# keyboardDesignV1.net
KiCad netlist of a schematic drawn in EAGLE
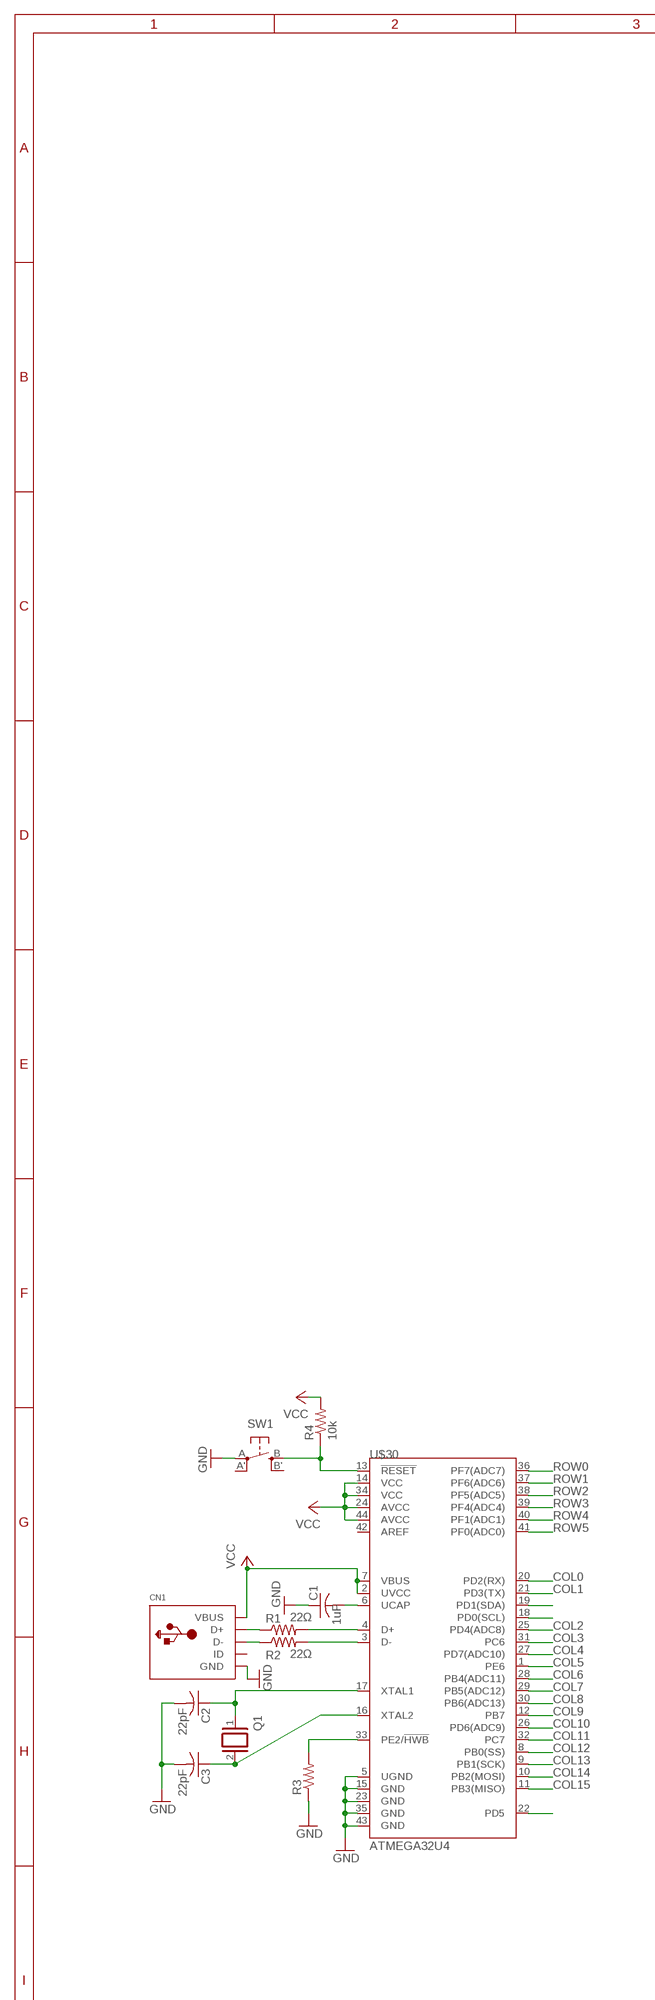
[diagram p0: schematic, sheet 1, part 1 of 2]
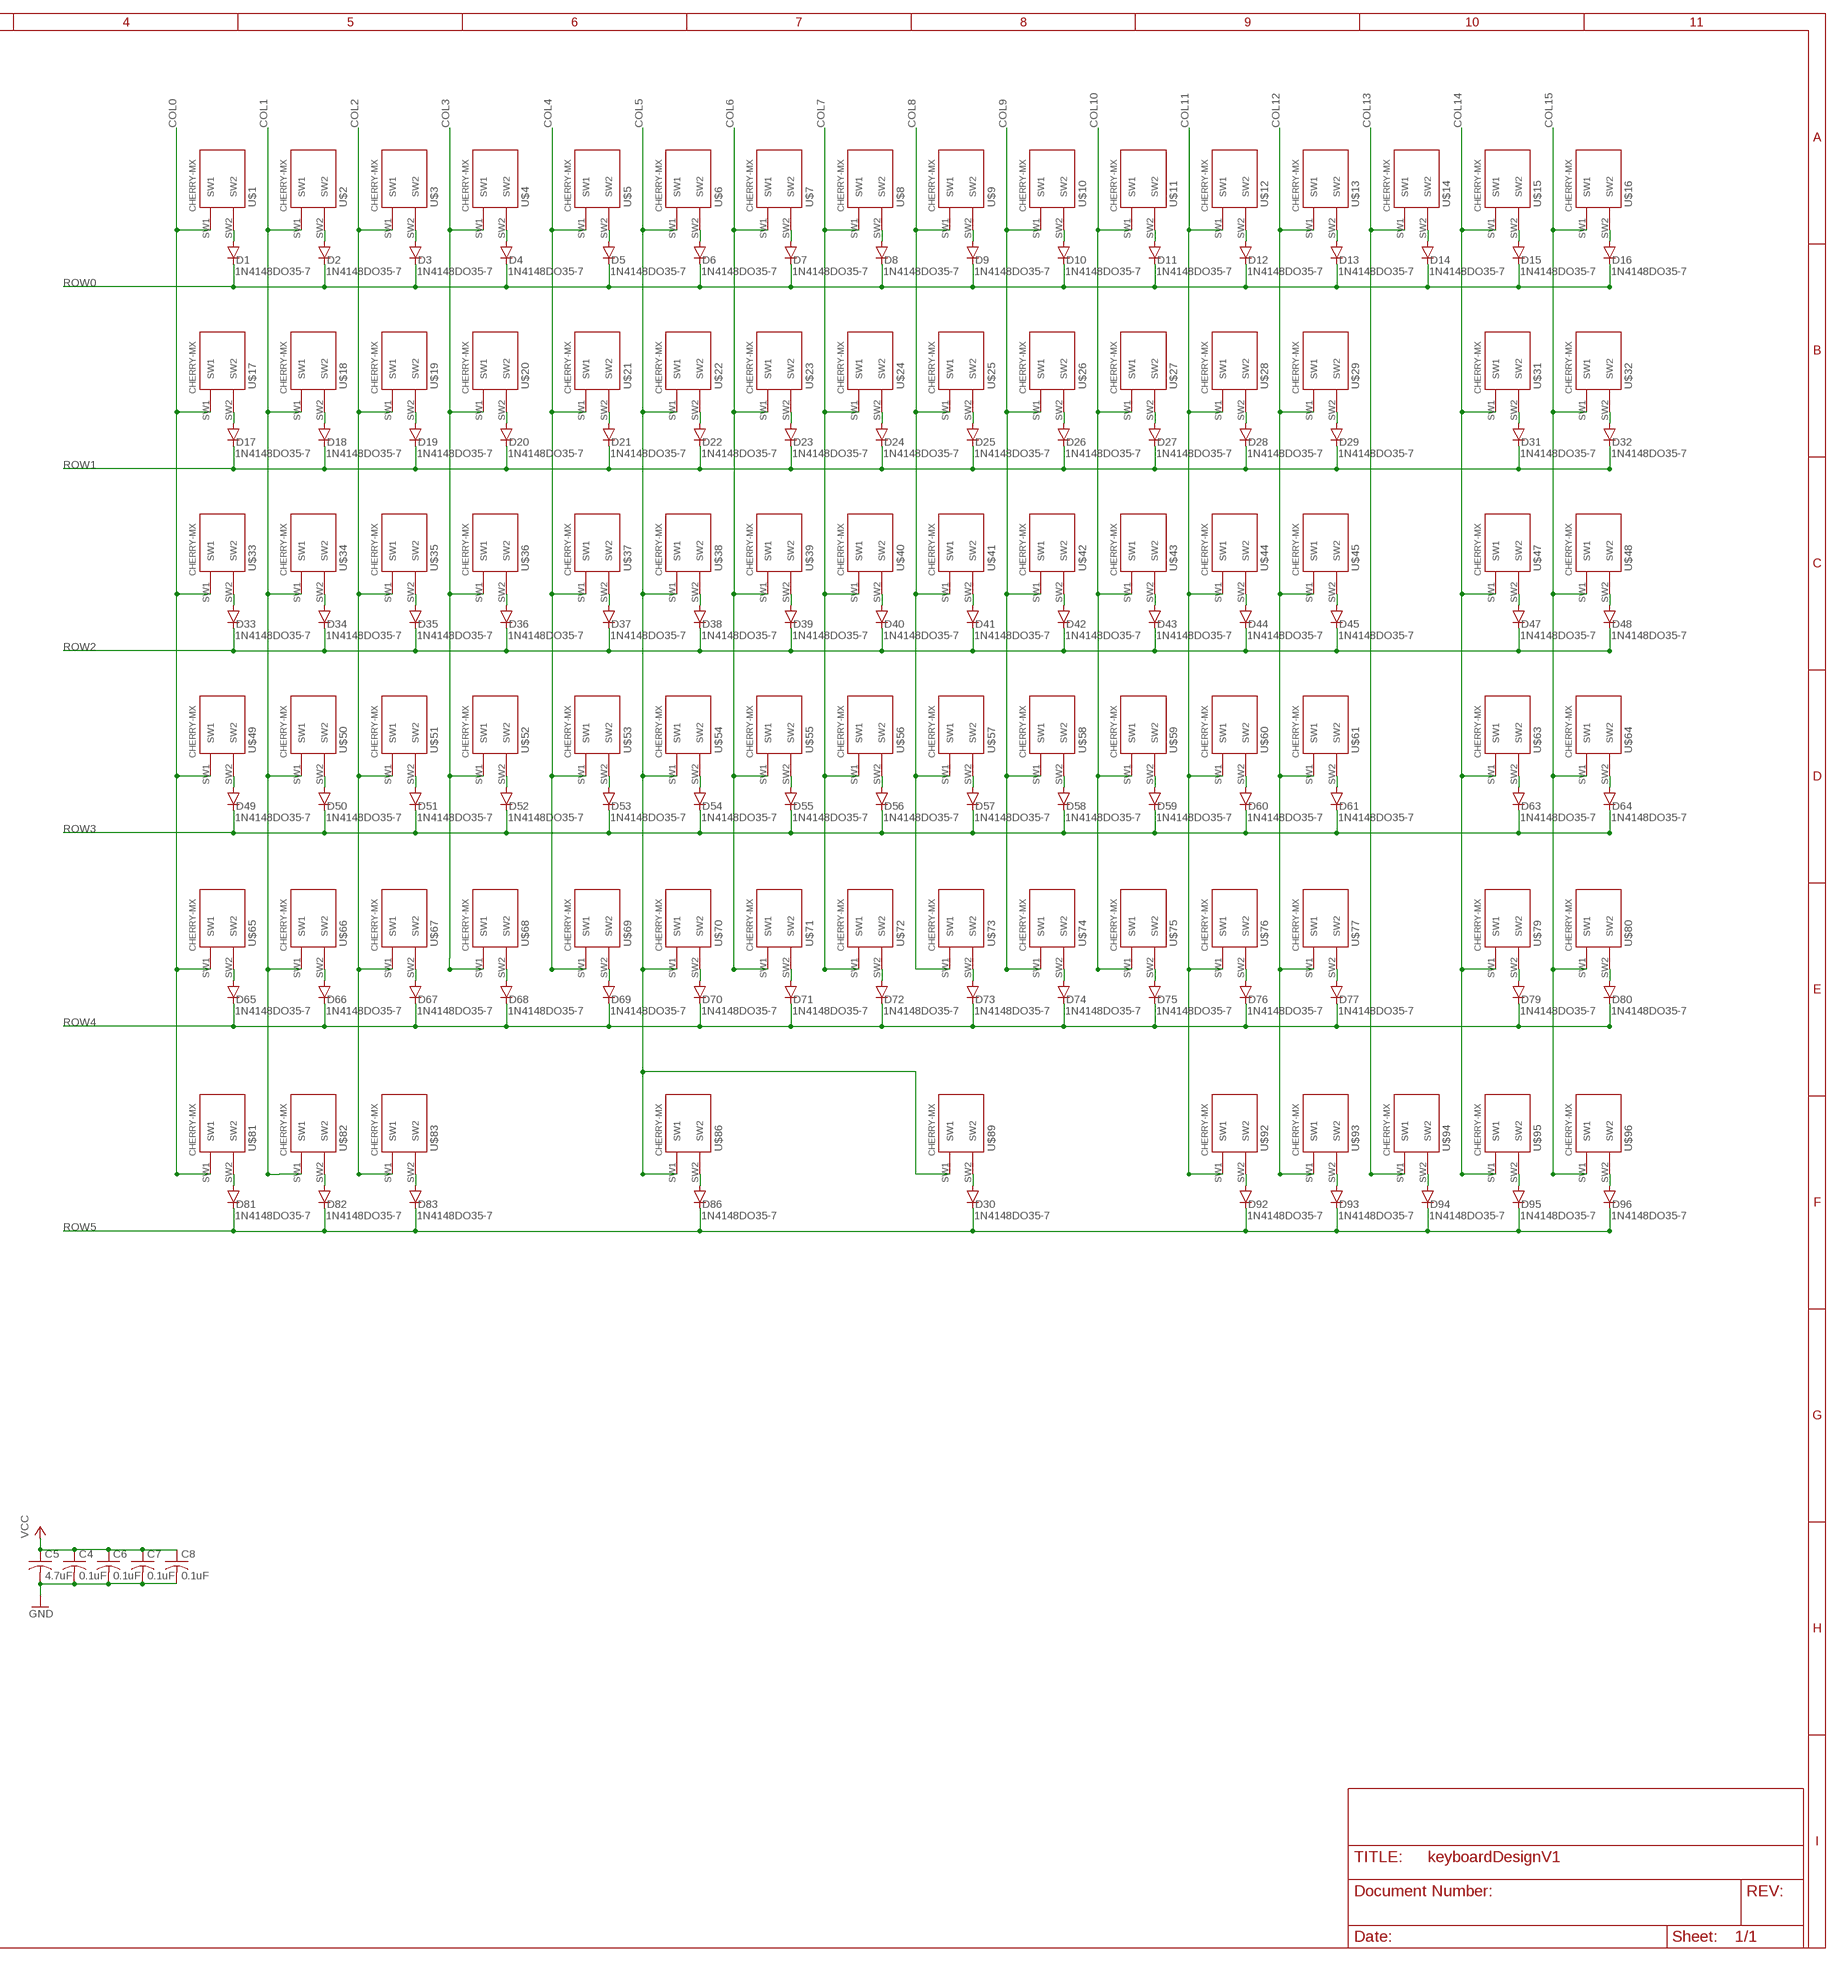
[diagram p1: schematic, sheet 1, part 2 of 2]

(export (version "E")
  (design (tool "Eeschema 10.0.6"))
  (components
    (comp (ref "C1")
      (value "1uF")
      (footprint "eagle-import:C025-025X050")
      (libsource (lib "eagle-import") (part "C-US025-025X050"))
    )
    (comp (ref "C2")
      (value "22pF")
      (footprint "eagle-import:C025-025X050")
      (libsource (lib "eagle-import") (part "C-US025-025X050"))
    )
    (comp (ref "C3")
      (value "22pF")
      (footprint "eagle-import:C025-025X050")
      (libsource (lib "eagle-import") (part "C-US025-025X050"))
    )
    (comp (ref "C4")
      (value "0.1uF")
      (footprint "eagle-import:C025-025X050")
      (libsource (lib "eagle-import") (part "C-US025-025X050"))
    )
    (comp (ref "C5")
      (value "4.7uF")
      (footprint "eagle-import:C025-025X050")
      (libsource (lib "eagle-import") (part "C-US025-025X050"))
    )
    (comp (ref "C6")
      (value "0.1uF")
      (footprint "eagle-import:C025-025X050")
      (libsource (lib "eagle-import") (part "C-US025-025X050"))
    )
    (comp (ref "C7")
      (value "0.1uF")
      (footprint "eagle-import:C025-025X050")
      (libsource (lib "eagle-import") (part "C-US025-025X050"))
    )
    (comp (ref "C8")
      (value "0.1uF")
      (footprint "eagle-import:C025-025X050")
      (libsource (lib "eagle-import") (part "C-US025-025X050"))
    )
    (comp (ref "CN1")
      (value "USBTHM")
      (footprint "eagle-import:USB-MINIB-THM")
      (libsource (lib "eagle-import") (part "USBTHM"))
    )
    (comp (ref "D1")
      (value "1N4148DO35-7")
      (footprint "eagle-import:DO35-7")
      (libsource (lib "eagle-import") (part "1N4148DO35-7"))
    )
    (comp (ref "D2")
      (value "1N4148DO35-7")
      (footprint "eagle-import:DO35-7")
      (libsource (lib "eagle-import") (part "1N4148DO35-7"))
    )
    (comp (ref "D3")
      (value "1N4148DO35-7")
      (footprint "eagle-import:DO35-7")
      (libsource (lib "eagle-import") (part "1N4148DO35-7"))
    )
    (comp (ref "D4")
      (value "1N4148DO35-7")
      (footprint "eagle-import:DO35-7")
      (libsource (lib "eagle-import") (part "1N4148DO35-7"))
    )
    (comp (ref "D5")
      (value "1N4148DO35-7")
      (footprint "eagle-import:DO35-7")
      (libsource (lib "eagle-import") (part "1N4148DO35-7"))
    )
    (comp (ref "D6")
      (value "1N4148DO35-7")
      (footprint "eagle-import:DO35-7")
      (libsource (lib "eagle-import") (part "1N4148DO35-7"))
    )
    (comp (ref "D7")
      (value "1N4148DO35-7")
      (footprint "eagle-import:DO35-7")
      (libsource (lib "eagle-import") (part "1N4148DO35-7"))
    )
    (comp (ref "D8")
      (value "1N4148DO35-7")
      (footprint "eagle-import:DO35-7")
      (libsource (lib "eagle-import") (part "1N4148DO35-7"))
    )
    (comp (ref "D9")
      (value "1N4148DO35-7")
      (footprint "eagle-import:DO35-7")
      (libsource (lib "eagle-import") (part "1N4148DO35-7"))
    )
    (comp (ref "D10")
      (value "1N4148DO35-7")
      (footprint "eagle-import:DO35-7")
      (libsource (lib "eagle-import") (part "1N4148DO35-7"))
    )
    (comp (ref "D11")
      (value "1N4148DO35-7")
      (footprint "eagle-import:DO35-7")
      (libsource (lib "eagle-import") (part "1N4148DO35-7"))
    )
    (comp (ref "D12")
      (value "1N4148DO35-7")
      (footprint "eagle-import:DO35-7")
      (libsource (lib "eagle-import") (part "1N4148DO35-7"))
    )
    (comp (ref "D13")
      (value "1N4148DO35-7")
      (footprint "eagle-import:DO35-7")
      (libsource (lib "eagle-import") (part "1N4148DO35-7"))
    )
    (comp (ref "D14")
      (value "1N4148DO35-7")
      (footprint "eagle-import:DO35-7")
      (libsource (lib "eagle-import") (part "1N4148DO35-7"))
    )
    (comp (ref "D15")
      (value "1N4148DO35-7")
      (footprint "eagle-import:DO35-7")
      (libsource (lib "eagle-import") (part "1N4148DO35-7"))
    )
    (comp (ref "D16")
      (value "1N4148DO35-7")
      (footprint "eagle-import:DO35-7")
      (libsource (lib "eagle-import") (part "1N4148DO35-7"))
    )
    (comp (ref "D17")
      (value "1N4148DO35-7")
      (footprint "eagle-import:DO35-7")
      (libsource (lib "eagle-import") (part "1N4148DO35-7"))
    )
    (comp (ref "D18")
      (value "1N4148DO35-7")
      (footprint "eagle-import:DO35-7")
      (libsource (lib "eagle-import") (part "1N4148DO35-7"))
    )
    (comp (ref "D19")
      (value "1N4148DO35-7")
      (footprint "eagle-import:DO35-7")
      (libsource (lib "eagle-import") (part "1N4148DO35-7"))
    )
    (comp (ref "D20")
      (value "1N4148DO35-7")
      (footprint "eagle-import:DO35-7")
      (libsource (lib "eagle-import") (part "1N4148DO35-7"))
    )
    (comp (ref "D21")
      (value "1N4148DO35-7")
      (footprint "eagle-import:DO35-7")
      (libsource (lib "eagle-import") (part "1N4148DO35-7"))
    )
    (comp (ref "D22")
      (value "1N4148DO35-7")
      (footprint "eagle-import:DO35-7")
      (libsource (lib "eagle-import") (part "1N4148DO35-7"))
    )
    (comp (ref "D23")
      (value "1N4148DO35-7")
      (footprint "eagle-import:DO35-7")
      (libsource (lib "eagle-import") (part "1N4148DO35-7"))
    )
    (comp (ref "D24")
      (value "1N4148DO35-7")
      (footprint "eagle-import:DO35-7")
      (libsource (lib "eagle-import") (part "1N4148DO35-7"))
    )
    (comp (ref "D25")
      (value "1N4148DO35-7")
      (footprint "eagle-import:DO35-7")
      (libsource (lib "eagle-import") (part "1N4148DO35-7"))
    )
    (comp (ref "D26")
      (value "1N4148DO35-7")
      (footprint "eagle-import:DO35-7")
      (libsource (lib "eagle-import") (part "1N4148DO35-7"))
    )
    (comp (ref "D27")
      (value "1N4148DO35-7")
      (footprint "eagle-import:DO35-7")
      (libsource (lib "eagle-import") (part "1N4148DO35-7"))
    )
    (comp (ref "D28")
      (value "1N4148DO35-7")
      (footprint "eagle-import:DO35-7")
      (libsource (lib "eagle-import") (part "1N4148DO35-7"))
    )
    (comp (ref "D29")
      (value "1N4148DO35-7")
      (footprint "eagle-import:DO35-7")
      (libsource (lib "eagle-import") (part "1N4148DO35-7"))
    )
    (comp (ref "D30")
      (value "1N4148DO35-7")
      (footprint "eagle-import:DO35-7")
      (libsource (lib "eagle-import") (part "1N4148DO35-7"))
    )
    (comp (ref "D31")
      (value "1N4148DO35-7")
      (footprint "eagle-import:DO35-7")
      (libsource (lib "eagle-import") (part "1N4148DO35-7"))
    )
    (comp (ref "D32")
      (value "1N4148DO35-7")
      (footprint "eagle-import:DO35-7")
      (libsource (lib "eagle-import") (part "1N4148DO35-7"))
    )
    (comp (ref "D33")
      (value "1N4148DO35-7")
      (footprint "eagle-import:DO35-7")
      (libsource (lib "eagle-import") (part "1N4148DO35-7"))
    )
    (comp (ref "D34")
      (value "1N4148DO35-7")
      (footprint "eagle-import:DO35-7")
      (libsource (lib "eagle-import") (part "1N4148DO35-7"))
    )
    (comp (ref "D35")
      (value "1N4148DO35-7")
      (footprint "eagle-import:DO35-7")
      (libsource (lib "eagle-import") (part "1N4148DO35-7"))
    )
    (comp (ref "D36")
      (value "1N4148DO35-7")
      (footprint "eagle-import:DO35-7")
      (libsource (lib "eagle-import") (part "1N4148DO35-7"))
    )
    (comp (ref "D37")
      (value "1N4148DO35-7")
      (footprint "eagle-import:DO35-7")
      (libsource (lib "eagle-import") (part "1N4148DO35-7"))
    )
    (comp (ref "D38")
      (value "1N4148DO35-7")
      (footprint "eagle-import:DO35-7")
      (libsource (lib "eagle-import") (part "1N4148DO35-7"))
    )
    (comp (ref "D39")
      (value "1N4148DO35-7")
      (footprint "eagle-import:DO35-7")
      (libsource (lib "eagle-import") (part "1N4148DO35-7"))
    )
    (comp (ref "D40")
      (value "1N4148DO35-7")
      (footprint "eagle-import:DO35-7")
      (libsource (lib "eagle-import") (part "1N4148DO35-7"))
    )
    (comp (ref "D41")
      (value "1N4148DO35-7")
      (footprint "eagle-import:DO35-7")
      (libsource (lib "eagle-import") (part "1N4148DO35-7"))
    )
    (comp (ref "D42")
      (value "1N4148DO35-7")
      (footprint "eagle-import:DO35-7")
      (libsource (lib "eagle-import") (part "1N4148DO35-7"))
    )
    (comp (ref "D43")
      (value "1N4148DO35-7")
      (footprint "eagle-import:DO35-7")
      (libsource (lib "eagle-import") (part "1N4148DO35-7"))
    )
    (comp (ref "D44")
      (value "1N4148DO35-7")
      (footprint "eagle-import:DO35-7")
      (libsource (lib "eagle-import") (part "1N4148DO35-7"))
    )
    (comp (ref "D45")
      (value "1N4148DO35-7")
      (footprint "eagle-import:DO35-7")
      (libsource (lib "eagle-import") (part "1N4148DO35-7"))
    )
    (comp (ref "D47")
      (value "1N4148DO35-7")
      (footprint "eagle-import:DO35-7")
      (libsource (lib "eagle-import") (part "1N4148DO35-7"))
    )
    (comp (ref "D48")
      (value "1N4148DO35-7")
      (footprint "eagle-import:DO35-7")
      (libsource (lib "eagle-import") (part "1N4148DO35-7"))
    )
    (comp (ref "D49")
      (value "1N4148DO35-7")
      (footprint "eagle-import:DO35-7")
      (libsource (lib "eagle-import") (part "1N4148DO35-7"))
    )
    (comp (ref "D50")
      (value "1N4148DO35-7")
      (footprint "eagle-import:DO35-7")
      (libsource (lib "eagle-import") (part "1N4148DO35-7"))
    )
    (comp (ref "D51")
      (value "1N4148DO35-7")
      (footprint "eagle-import:DO35-7")
      (libsource (lib "eagle-import") (part "1N4148DO35-7"))
    )
    (comp (ref "D52")
      (value "1N4148DO35-7")
      (footprint "eagle-import:DO35-7")
      (libsource (lib "eagle-import") (part "1N4148DO35-7"))
    )
    (comp (ref "D53")
      (value "1N4148DO35-7")
      (footprint "eagle-import:DO35-7")
      (libsource (lib "eagle-import") (part "1N4148DO35-7"))
    )
    (comp (ref "D54")
      (value "1N4148DO35-7")
      (footprint "eagle-import:DO35-7")
      (libsource (lib "eagle-import") (part "1N4148DO35-7"))
    )
    (comp (ref "D55")
      (value "1N4148DO35-7")
      (footprint "eagle-import:DO35-7")
      (libsource (lib "eagle-import") (part "1N4148DO35-7"))
    )
    (comp (ref "D56")
      (value "1N4148DO35-7")
      (footprint "eagle-import:DO35-7")
      (libsource (lib "eagle-import") (part "1N4148DO35-7"))
    )
    (comp (ref "D57")
      (value "1N4148DO35-7")
      (footprint "eagle-import:DO35-7")
      (libsource (lib "eagle-import") (part "1N4148DO35-7"))
    )
    (comp (ref "D58")
      (value "1N4148DO35-7")
      (footprint "eagle-import:DO35-7")
      (libsource (lib "eagle-import") (part "1N4148DO35-7"))
    )
    (comp (ref "D59")
      (value "1N4148DO35-7")
      (footprint "eagle-import:DO35-7")
      (libsource (lib "eagle-import") (part "1N4148DO35-7"))
    )
    (comp (ref "D60")
      (value "1N4148DO35-7")
      (footprint "eagle-import:DO35-7")
      (libsource (lib "eagle-import") (part "1N4148DO35-7"))
    )
    (comp (ref "D61")
      (value "1N4148DO35-7")
      (footprint "eagle-import:DO35-7")
      (libsource (lib "eagle-import") (part "1N4148DO35-7"))
    )
    (comp (ref "D63")
      (value "1N4148DO35-7")
      (footprint "eagle-import:DO35-7")
      (libsource (lib "eagle-import") (part "1N4148DO35-7"))
    )
    (comp (ref "D64")
      (value "1N4148DO35-7")
      (footprint "eagle-import:DO35-7")
      (libsource (lib "eagle-import") (part "1N4148DO35-7"))
    )
    (comp (ref "D65")
      (value "1N4148DO35-7")
      (footprint "eagle-import:DO35-7")
      (libsource (lib "eagle-import") (part "1N4148DO35-7"))
    )
    (comp (ref "D66")
      (value "1N4148DO35-7")
      (footprint "eagle-import:DO35-7")
      (libsource (lib "eagle-import") (part "1N4148DO35-7"))
    )
    (comp (ref "D67")
      (value "1N4148DO35-7")
      (footprint "eagle-import:DO35-7")
      (libsource (lib "eagle-import") (part "1N4148DO35-7"))
    )
    (comp (ref "D68")
      (value "1N4148DO35-7")
      (footprint "eagle-import:DO35-7")
      (libsource (lib "eagle-import") (part "1N4148DO35-7"))
    )
    (comp (ref "D69")
      (value "1N4148DO35-7")
      (footprint "eagle-import:DO35-7")
      (libsource (lib "eagle-import") (part "1N4148DO35-7"))
    )
    (comp (ref "D70")
      (value "1N4148DO35-7")
      (footprint "eagle-import:DO35-7")
      (libsource (lib "eagle-import") (part "1N4148DO35-7"))
    )
    (comp (ref "D71")
      (value "1N4148DO35-7")
      (footprint "eagle-import:DO35-7")
      (libsource (lib "eagle-import") (part "1N4148DO35-7"))
    )
    (comp (ref "D72")
      (value "1N4148DO35-7")
      (footprint "eagle-import:DO35-7")
      (libsource (lib "eagle-import") (part "1N4148DO35-7"))
    )
    (comp (ref "D73")
      (value "1N4148DO35-7")
      (footprint "eagle-import:DO35-7")
      (libsource (lib "eagle-import") (part "1N4148DO35-7"))
    )
    (comp (ref "D74")
      (value "1N4148DO35-7")
      (footprint "eagle-import:DO35-7")
      (libsource (lib "eagle-import") (part "1N4148DO35-7"))
    )
    (comp (ref "D75")
      (value "1N4148DO35-7")
      (footprint "eagle-import:DO35-7")
      (libsource (lib "eagle-import") (part "1N4148DO35-7"))
    )
    (comp (ref "D76")
      (value "1N4148DO35-7")
      (footprint "eagle-import:DO35-7")
      (libsource (lib "eagle-import") (part "1N4148DO35-7"))
    )
    (comp (ref "D77")
      (value "1N4148DO35-7")
      (footprint "eagle-import:DO35-7")
      (libsource (lib "eagle-import") (part "1N4148DO35-7"))
    )
    (comp (ref "D79")
      (value "1N4148DO35-7")
      (footprint "eagle-import:DO35-7")
      (libsource (lib "eagle-import") (part "1N4148DO35-7"))
    )
    (comp (ref "D80")
      (value "1N4148DO35-7")
      (footprint "eagle-import:DO35-7")
      (libsource (lib "eagle-import") (part "1N4148DO35-7"))
    )
    (comp (ref "D81")
      (value "1N4148DO35-7")
      (footprint "eagle-import:DO35-7")
      (libsource (lib "eagle-import") (part "1N4148DO35-7"))
    )
    (comp (ref "D82")
      (value "1N4148DO35-7")
      (footprint "eagle-import:DO35-7")
      (libsource (lib "eagle-import") (part "1N4148DO35-7"))
    )
    (comp (ref "D83")
      (value "1N4148DO35-7")
      (footprint "eagle-import:DO35-7")
      (libsource (lib "eagle-import") (part "1N4148DO35-7"))
    )
    (comp (ref "D86")
      (value "1N4148DO35-7")
      (footprint "eagle-import:DO35-7")
      (libsource (lib "eagle-import") (part "1N4148DO35-7"))
    )
    (comp (ref "D92")
      (value "1N4148DO35-7")
      (footprint "eagle-import:DO35-7")
      (libsource (lib "eagle-import") (part "1N4148DO35-7"))
    )
    (comp (ref "D93")
      (value "1N4148DO35-7")
      (footprint "eagle-import:DO35-7")
      (libsource (lib "eagle-import") (part "1N4148DO35-7"))
    )
    (comp (ref "D94")
      (value "1N4148DO35-7")
      (footprint "eagle-import:DO35-7")
      (libsource (lib "eagle-import") (part "1N4148DO35-7"))
    )
    (comp (ref "D95")
      (value "1N4148DO35-7")
      (footprint "eagle-import:DO35-7")
      (libsource (lib "eagle-import") (part "1N4148DO35-7"))
    )
    (comp (ref "D96")
      (value "1N4148DO35-7")
      (footprint "eagle-import:DO35-7")
      (libsource (lib "eagle-import") (part "1N4148DO35-7"))
    )
    (comp (ref "Q1")
      (value "XTAL/S")
      (footprint "eagle-import:QS")
      (libsource (lib "eagle-import") (part "XTAL/S"))
    )
    (comp (ref "R1")
      (value "22Ω")
      (footprint "eagle-import:0204_7")
      (libsource (lib "eagle-import") (part "R-US_0204/7"))
    )
    (comp (ref "R2")
      (value "22Ω")
      (footprint "eagle-import:0204_7")
      (libsource (lib "eagle-import") (part "R-US_0204/7"))
    )
    (comp (ref "R3")
      (value "R-US_0204/7")
      (footprint "eagle-import:0204_7")
      (libsource (lib "eagle-import") (part "R-US_0204/7"))
    )
    (comp (ref "R4")
      (value "10k")
      (footprint "eagle-import:0204_7")
      (libsource (lib "eagle-import") (part "R-US_0204/7"))
    )
    (comp (ref "SW1")
      (value "SPST_TACT-EVQQ2")
      (footprint "eagle-import:EVQ-Q2")
      (libsource (lib "eagle-import") (part "SPST_TACT-EVQQ2"))
    )
    (comp (ref "U$1")
      (value "CHERRY-MXSTANDARD")
      (footprint "eagle-import:CHERRY-MX")
      (libsource (lib "eagle-import") (part "CHERRY-MXSTANDARD"))
    )
    (comp (ref "U$2")
      (value "CHERRY-MXSTANDARD")
      (footprint "eagle-import:CHERRY-MX")
      (libsource (lib "eagle-import") (part "CHERRY-MXSTANDARD"))
    )
    (comp (ref "U$3")
      (value "CHERRY-MXSTANDARD")
      (footprint "eagle-import:CHERRY-MX")
      (libsource (lib "eagle-import") (part "CHERRY-MXSTANDARD"))
    )
    (comp (ref "U$4")
      (value "CHERRY-MXSTANDARD")
      (footprint "eagle-import:CHERRY-MX")
      (libsource (lib "eagle-import") (part "CHERRY-MXSTANDARD"))
    )
    (comp (ref "U$5")
      (value "CHERRY-MXSTANDARD")
      (footprint "eagle-import:CHERRY-MX")
      (libsource (lib "eagle-import") (part "CHERRY-MXSTANDARD"))
    )
    (comp (ref "U$6")
      (value "CHERRY-MXSTANDARD")
      (footprint "eagle-import:CHERRY-MX")
      (libsource (lib "eagle-import") (part "CHERRY-MXSTANDARD"))
    )
    (comp (ref "U$7")
      (value "CHERRY-MXSTANDARD")
      (footprint "eagle-import:CHERRY-MX")
      (libsource (lib "eagle-import") (part "CHERRY-MXSTANDARD"))
    )
    (comp (ref "U$8")
      (value "CHERRY-MXSTANDARD")
      (footprint "eagle-import:CHERRY-MX")
      (libsource (lib "eagle-import") (part "CHERRY-MXSTANDARD"))
    )
    (comp (ref "U$9")
      (value "CHERRY-MXSTANDARD")
      (footprint "eagle-import:CHERRY-MX")
      (libsource (lib "eagle-import") (part "CHERRY-MXSTANDARD"))
    )
    (comp (ref "U$10")
      (value "CHERRY-MXSTANDARD")
      (footprint "eagle-import:CHERRY-MX")
      (libsource (lib "eagle-import") (part "CHERRY-MXSTANDARD"))
    )
    (comp (ref "U$11")
      (value "CHERRY-MXSTANDARD")
      (footprint "eagle-import:CHERRY-MX")
      (libsource (lib "eagle-import") (part "CHERRY-MXSTANDARD"))
    )
    (comp (ref "U$12")
      (value "CHERRY-MXSTANDARD")
      (footprint "eagle-import:CHERRY-MX")
      (libsource (lib "eagle-import") (part "CHERRY-MXSTANDARD"))
    )
    (comp (ref "U$13")
      (value "CHERRY-MXSTANDARD")
      (footprint "eagle-import:CHERRY-MX")
      (libsource (lib "eagle-import") (part "CHERRY-MXSTANDARD"))
    )
    (comp (ref "U$14")
      (value "CHERRY-MXSTANDARD")
      (footprint "eagle-import:CHERRY-MX")
      (libsource (lib "eagle-import") (part "CHERRY-MXSTANDARD"))
    )
    (comp (ref "U$15")
      (value "CHERRY-MXSTANDARD")
      (footprint "eagle-import:CHERRY-MX")
      (libsource (lib "eagle-import") (part "CHERRY-MXSTANDARD"))
    )
    (comp (ref "U$16")
      (value "CHERRY-MXSTANDARD")
      (footprint "eagle-import:CHERRY-MX")
      (libsource (lib "eagle-import") (part "CHERRY-MXSTANDARD"))
    )
    (comp (ref "U$17")
      (value "CHERRY-MXSTANDARD")
      (footprint "eagle-import:CHERRY-MX")
      (libsource (lib "eagle-import") (part "CHERRY-MXSTANDARD"))
    )
    (comp (ref "U$18")
      (value "CHERRY-MXSTANDARD")
      (footprint "eagle-import:CHERRY-MX")
      (libsource (lib "eagle-import") (part "CHERRY-MXSTANDARD"))
    )
    (comp (ref "U$19")
      (value "CHERRY-MXSTANDARD")
      (footprint "eagle-import:CHERRY-MX")
      (libsource (lib "eagle-import") (part "CHERRY-MXSTANDARD"))
    )
    (comp (ref "U$20")
      (value "CHERRY-MXSTANDARD")
      (footprint "eagle-import:CHERRY-MX")
      (libsource (lib "eagle-import") (part "CHERRY-MXSTANDARD"))
    )
    (comp (ref "U$21")
      (value "CHERRY-MXSTANDARD")
      (footprint "eagle-import:CHERRY-MX")
      (libsource (lib "eagle-import") (part "CHERRY-MXSTANDARD"))
    )
    (comp (ref "U$22")
      (value "CHERRY-MXSTANDARD")
      (footprint "eagle-import:CHERRY-MX")
      (libsource (lib "eagle-import") (part "CHERRY-MXSTANDARD"))
    )
    (comp (ref "U$23")
      (value "CHERRY-MXSTANDARD")
      (footprint "eagle-import:CHERRY-MX")
      (libsource (lib "eagle-import") (part "CHERRY-MXSTANDARD"))
    )
    (comp (ref "U$24")
      (value "CHERRY-MXSTANDARD")
      (footprint "eagle-import:CHERRY-MX")
      (libsource (lib "eagle-import") (part "CHERRY-MXSTANDARD"))
    )
    (comp (ref "U$25")
      (value "CHERRY-MXSTANDARD")
      (footprint "eagle-import:CHERRY-MX")
      (libsource (lib "eagle-import") (part "CHERRY-MXSTANDARD"))
    )
    (comp (ref "U$26")
      (value "CHERRY-MXSTANDARD")
      (footprint "eagle-import:CHERRY-MX")
      (libsource (lib "eagle-import") (part "CHERRY-MXSTANDARD"))
    )
    (comp (ref "U$27")
      (value "CHERRY-MXSTANDARD")
      (footprint "eagle-import:CHERRY-MX")
      (libsource (lib "eagle-import") (part "CHERRY-MXSTANDARD"))
    )
    (comp (ref "U$28")
      (value "CHERRY-MXSTANDARD")
      (footprint "eagle-import:CHERRY-MX")
      (libsource (lib "eagle-import") (part "CHERRY-MXSTANDARD"))
    )
    (comp (ref "U$29")
      (value "CHERRY-MXSTANDARD")
      (footprint "eagle-import:CHERRY-MX")
      (libsource (lib "eagle-import") (part "CHERRY-MXSTANDARD"))
    )
    (comp (ref "U$30")
      (value "ATMEGA32U4")
      (footprint "eagle-import:QFN-44-NOPAD_1_1")
      (libsource (lib "eagle-import") (part "ATMEGA32U41{colon}1"))
    )
    (comp (ref "U$31")
      (value "CHERRY-MXSTANDARD")
      (footprint "eagle-import:CHERRY-MX")
      (libsource (lib "eagle-import") (part "CHERRY-MXSTANDARD"))
    )
    (comp (ref "U$32")
      (value "CHERRY-MXSTANDARD")
      (footprint "eagle-import:CHERRY-MX")
      (libsource (lib "eagle-import") (part "CHERRY-MXSTANDARD"))
    )
    (comp (ref "U$33")
      (value "CHERRY-MXSTANDARD")
      (footprint "eagle-import:CHERRY-MX")
      (libsource (lib "eagle-import") (part "CHERRY-MXSTANDARD"))
    )
    (comp (ref "U$34")
      (value "CHERRY-MXSTANDARD")
      (footprint "eagle-import:CHERRY-MX")
      (libsource (lib "eagle-import") (part "CHERRY-MXSTANDARD"))
    )
    (comp (ref "U$35")
      (value "CHERRY-MXSTANDARD")
      (footprint "eagle-import:CHERRY-MX")
      (libsource (lib "eagle-import") (part "CHERRY-MXSTANDARD"))
    )
    (comp (ref "U$36")
      (value "CHERRY-MXSTANDARD")
      (footprint "eagle-import:CHERRY-MX")
      (libsource (lib "eagle-import") (part "CHERRY-MXSTANDARD"))
    )
    (comp (ref "U$37")
      (value "CHERRY-MXSTANDARD")
      (footprint "eagle-import:CHERRY-MX")
      (libsource (lib "eagle-import") (part "CHERRY-MXSTANDARD"))
    )
    (comp (ref "U$38")
      (value "CHERRY-MXSTANDARD")
      (footprint "eagle-import:CHERRY-MX")
      (libsource (lib "eagle-import") (part "CHERRY-MXSTANDARD"))
    )
    (comp (ref "U$39")
      (value "CHERRY-MXSTANDARD")
      (footprint "eagle-import:CHERRY-MX")
      (libsource (lib "eagle-import") (part "CHERRY-MXSTANDARD"))
    )
    (comp (ref "U$40")
      (value "CHERRY-MXSTANDARD")
      (footprint "eagle-import:CHERRY-MX")
      (libsource (lib "eagle-import") (part "CHERRY-MXSTANDARD"))
    )
    (comp (ref "U$41")
      (value "CHERRY-MXSTANDARD")
      (footprint "eagle-import:CHERRY-MX")
      (libsource (lib "eagle-import") (part "CHERRY-MXSTANDARD"))
    )
    (comp (ref "U$42")
      (value "CHERRY-MXSTANDARD")
      (footprint "eagle-import:CHERRY-MX")
      (libsource (lib "eagle-import") (part "CHERRY-MXSTANDARD"))
    )
    (comp (ref "U$43")
      (value "CHERRY-MXSTANDARD")
      (footprint "eagle-import:CHERRY-MX")
      (libsource (lib "eagle-import") (part "CHERRY-MXSTANDARD"))
    )
    (comp (ref "U$44")
      (value "CHERRY-MXSTANDARD")
      (footprint "eagle-import:CHERRY-MX")
      (libsource (lib "eagle-import") (part "CHERRY-MXSTANDARD"))
    )
    (comp (ref "U$45")
      (value "CHERRY-MXSTANDARD")
      (footprint "eagle-import:CHERRY-MX")
      (libsource (lib "eagle-import") (part "CHERRY-MXSTANDARD"))
    )
    (comp (ref "U$47")
      (value "CHERRY-MXSTANDARD")
      (footprint "eagle-import:CHERRY-MX")
      (libsource (lib "eagle-import") (part "CHERRY-MXSTANDARD"))
    )
    (comp (ref "U$48")
      (value "CHERRY-MXSTANDARD")
      (footprint "eagle-import:CHERRY-MX")
      (libsource (lib "eagle-import") (part "CHERRY-MXSTANDARD"))
    )
    (comp (ref "U$49")
      (value "CHERRY-MXSTANDARD")
      (footprint "eagle-import:CHERRY-MX")
      (libsource (lib "eagle-import") (part "CHERRY-MXSTANDARD"))
    )
    (comp (ref "U$50")
      (value "CHERRY-MXSTANDARD")
      (footprint "eagle-import:CHERRY-MX")
      (libsource (lib "eagle-import") (part "CHERRY-MXSTANDARD"))
    )
    (comp (ref "U$51")
      (value "CHERRY-MXSTANDARD")
      (footprint "eagle-import:CHERRY-MX")
      (libsource (lib "eagle-import") (part "CHERRY-MXSTANDARD"))
    )
    (comp (ref "U$52")
      (value "CHERRY-MXSTANDARD")
      (footprint "eagle-import:CHERRY-MX")
      (libsource (lib "eagle-import") (part "CHERRY-MXSTANDARD"))
    )
    (comp (ref "U$53")
      (value "CHERRY-MXSTANDARD")
      (footprint "eagle-import:CHERRY-MX")
      (libsource (lib "eagle-import") (part "CHERRY-MXSTANDARD"))
    )
    (comp (ref "U$54")
      (value "CHERRY-MXSTANDARD")
      (footprint "eagle-import:CHERRY-MX")
      (libsource (lib "eagle-import") (part "CHERRY-MXSTANDARD"))
    )
    (comp (ref "U$55")
      (value "CHERRY-MXSTANDARD")
      (footprint "eagle-import:CHERRY-MX")
      (libsource (lib "eagle-import") (part "CHERRY-MXSTANDARD"))
    )
    (comp (ref "U$56")
      (value "CHERRY-MXSTANDARD")
      (footprint "eagle-import:CHERRY-MX")
      (libsource (lib "eagle-import") (part "CHERRY-MXSTANDARD"))
    )
    (comp (ref "U$57")
      (value "CHERRY-MXSTANDARD")
      (footprint "eagle-import:CHERRY-MX")
      (libsource (lib "eagle-import") (part "CHERRY-MXSTANDARD"))
    )
    (comp (ref "U$58")
      (value "CHERRY-MXSTANDARD")
      (footprint "eagle-import:CHERRY-MX")
      (libsource (lib "eagle-import") (part "CHERRY-MXSTANDARD"))
    )
    (comp (ref "U$59")
      (value "CHERRY-MXSTANDARD")
      (footprint "eagle-import:CHERRY-MX")
      (libsource (lib "eagle-import") (part "CHERRY-MXSTANDARD"))
    )
    (comp (ref "U$60")
      (value "CHERRY-MXSTANDARD")
      (footprint "eagle-import:CHERRY-MX")
      (libsource (lib "eagle-import") (part "CHERRY-MXSTANDARD"))
    )
    (comp (ref "U$61")
      (value "CHERRY-MXSTANDARD")
      (footprint "eagle-import:CHERRY-MX")
      (libsource (lib "eagle-import") (part "CHERRY-MXSTANDARD"))
    )
    (comp (ref "U$63")
      (value "CHERRY-MXSTANDARD")
      (footprint "eagle-import:CHERRY-MX")
      (libsource (lib "eagle-import") (part "CHERRY-MXSTANDARD"))
    )
    (comp (ref "U$64")
      (value "CHERRY-MXSTANDARD")
      (footprint "eagle-import:CHERRY-MX")
      (libsource (lib "eagle-import") (part "CHERRY-MXSTANDARD"))
    )
    (comp (ref "U$65")
      (value "CHERRY-MXSTANDARD")
      (footprint "eagle-import:CHERRY-MX")
      (libsource (lib "eagle-import") (part "CHERRY-MXSTANDARD"))
    )
    (comp (ref "U$66")
      (value "CHERRY-MXSTANDARD")
      (footprint "eagle-import:CHERRY-MX")
      (libsource (lib "eagle-import") (part "CHERRY-MXSTANDARD"))
    )
    (comp (ref "U$67")
      (value "CHERRY-MXSTANDARD")
      (footprint "eagle-import:CHERRY-MX")
      (libsource (lib "eagle-import") (part "CHERRY-MXSTANDARD"))
    )
    (comp (ref "U$68")
      (value "CHERRY-MXSTANDARD")
      (footprint "eagle-import:CHERRY-MX")
      (libsource (lib "eagle-import") (part "CHERRY-MXSTANDARD"))
    )
    (comp (ref "U$69")
      (value "CHERRY-MXSTANDARD")
      (footprint "eagle-import:CHERRY-MX")
      (libsource (lib "eagle-import") (part "CHERRY-MXSTANDARD"))
    )
    (comp (ref "U$70")
      (value "CHERRY-MXSTANDARD")
      (footprint "eagle-import:CHERRY-MX")
      (libsource (lib "eagle-import") (part "CHERRY-MXSTANDARD"))
    )
    (comp (ref "U$71")
      (value "CHERRY-MXSTANDARD")
      (footprint "eagle-import:CHERRY-MX")
      (libsource (lib "eagle-import") (part "CHERRY-MXSTANDARD"))
    )
    (comp (ref "U$72")
      (value "CHERRY-MXSTANDARD")
      (footprint "eagle-import:CHERRY-MX")
      (libsource (lib "eagle-import") (part "CHERRY-MXSTANDARD"))
    )
    (comp (ref "U$73")
      (value "CHERRY-MXSTANDARD")
      (footprint "eagle-import:CHERRY-MX")
      (libsource (lib "eagle-import") (part "CHERRY-MXSTANDARD"))
    )
    (comp (ref "U$74")
      (value "CHERRY-MXSTANDARD")
      (footprint "eagle-import:CHERRY-MX")
      (libsource (lib "eagle-import") (part "CHERRY-MXSTANDARD"))
    )
    (comp (ref "U$75")
      (value "CHERRY-MXSTANDARD")
      (footprint "eagle-import:CHERRY-MX")
      (libsource (lib "eagle-import") (part "CHERRY-MXSTANDARD"))
    )
    (comp (ref "U$76")
      (value "CHERRY-MXSTANDARD")
      (footprint "eagle-import:CHERRY-MX")
      (libsource (lib "eagle-import") (part "CHERRY-MXSTANDARD"))
    )
    (comp (ref "U$77")
      (value "CHERRY-MXSTANDARD")
      (footprint "eagle-import:CHERRY-MX")
      (libsource (lib "eagle-import") (part "CHERRY-MXSTANDARD"))
    )
    (comp (ref "U$79")
      (value "CHERRY-MXSTANDARD")
      (footprint "eagle-import:CHERRY-MX")
      (libsource (lib "eagle-import") (part "CHERRY-MXSTANDARD"))
    )
    (comp (ref "U$80")
      (value "CHERRY-MXSTANDARD")
      (footprint "eagle-import:CHERRY-MX")
      (libsource (lib "eagle-import") (part "CHERRY-MXSTANDARD"))
    )
    (comp (ref "U$81")
      (value "CHERRY-MXSTANDARD")
      (footprint "eagle-import:CHERRY-MX")
      (libsource (lib "eagle-import") (part "CHERRY-MXSTANDARD"))
    )
    (comp (ref "U$82")
      (value "CHERRY-MXSTANDARD")
      (footprint "eagle-import:CHERRY-MX")
      (libsource (lib "eagle-import") (part "CHERRY-MXSTANDARD"))
    )
    (comp (ref "U$83")
      (value "CHERRY-MXSTANDARD")
      (footprint "eagle-import:CHERRY-MX")
      (libsource (lib "eagle-import") (part "CHERRY-MXSTANDARD"))
    )
    (comp (ref "U$86")
      (value "CHERRY-MXSTANDARD")
      (footprint "eagle-import:CHERRY-MX")
      (libsource (lib "eagle-import") (part "CHERRY-MXSTANDARD"))
    )
    (comp (ref "U$89")
      (value "CHERRY-MXSTANDARD")
      (footprint "eagle-import:CHERRY-MX")
      (libsource (lib "eagle-import") (part "CHERRY-MXSTANDARD"))
    )
    (comp (ref "U$92")
      (value "CHERRY-MXSTANDARD")
      (footprint "eagle-import:CHERRY-MX")
      (libsource (lib "eagle-import") (part "CHERRY-MXSTANDARD"))
    )
    (comp (ref "U$93")
      (value "CHERRY-MXSTANDARD")
      (footprint "eagle-import:CHERRY-MX")
      (libsource (lib "eagle-import") (part "CHERRY-MXSTANDARD"))
    )
    (comp (ref "U$94")
      (value "CHERRY-MXSTANDARD")
      (footprint "eagle-import:CHERRY-MX")
      (libsource (lib "eagle-import") (part "CHERRY-MXSTANDARD"))
    )
    (comp (ref "U$95")
      (value "CHERRY-MXSTANDARD")
      (footprint "eagle-import:CHERRY-MX")
      (libsource (lib "eagle-import") (part "CHERRY-MXSTANDARD"))
    )
    (comp (ref "U$96")
      (value "CHERRY-MXSTANDARD")
      (footprint "eagle-import:CHERRY-MX")
      (libsource (lib "eagle-import") (part "CHERRY-MXSTANDARD"))
    )
  )
  (nets
    (net (code "1") (name "/COL0") (class "Default")
      (node (ref "U$1") (pin "SW1") (pinfunction "SW1_SW1") (pintype "bidirectional"))
      (node (ref "U$17") (pin "SW1") (pinfunction "SW1_SW1") (pintype "bidirectional"))
      (node (ref "U$30") (pin "20") (pinfunction "PD2(RX)_20") (pintype "bidirectional"))
      (node (ref "U$33") (pin "SW1") (pinfunction "SW1_SW1") (pintype "bidirectional"))
      (node (ref "U$49") (pin "SW1") (pinfunction "SW1_SW1") (pintype "bidirectional"))
      (node (ref "U$65") (pin "SW1") (pinfunction "SW1_SW1") (pintype "bidirectional"))
      (node (ref "U$81") (pin "SW1") (pinfunction "SW1_SW1") (pintype "bidirectional"))
    )
    (net (code "2") (name "/COL1") (class "Default")
      (node (ref "U$18") (pin "SW1") (pinfunction "SW1_SW1") (pintype "bidirectional"))
      (node (ref "U$2") (pin "SW1") (pinfunction "SW1_SW1") (pintype "bidirectional"))
      (node (ref "U$30") (pin "21") (pinfunction "PD3(TX)_21") (pintype "bidirectional"))
      (node (ref "U$34") (pin "SW1") (pinfunction "SW1_SW1") (pintype "bidirectional"))
      (node (ref "U$50") (pin "SW1") (pinfunction "SW1_SW1") (pintype "bidirectional"))
      (node (ref "U$66") (pin "SW1") (pinfunction "SW1_SW1") (pintype "bidirectional"))
      (node (ref "U$82") (pin "SW1") (pinfunction "SW1_SW1") (pintype "bidirectional"))
    )
    (net (code "3") (name "/COL2") (class "Default")
      (node (ref "U$19") (pin "SW1") (pinfunction "SW1_SW1") (pintype "bidirectional"))
      (node (ref "U$3") (pin "SW1") (pinfunction "SW1_SW1") (pintype "bidirectional"))
      (node (ref "U$30") (pin "25") (pinfunction "PD4(ADC8)_25") (pintype "bidirectional"))
      (node (ref "U$35") (pin "SW1") (pinfunction "SW1_SW1") (pintype "bidirectional"))
      (node (ref "U$51") (pin "SW1") (pinfunction "SW1_SW1") (pintype "bidirectional"))
      (node (ref "U$67") (pin "SW1") (pinfunction "SW1_SW1") (pintype "bidirectional"))
      (node (ref "U$83") (pin "SW1") (pinfunction "SW1_SW1") (pintype "bidirectional"))
    )
    (net (code "4") (name "/COL3") (class "Default")
      (node (ref "U$20") (pin "SW1") (pinfunction "SW1_SW1") (pintype "bidirectional"))
      (node (ref "U$30") (pin "31") (pinfunction "PC6_31") (pintype "bidirectional"))
      (node (ref "U$36") (pin "SW1") (pinfunction "SW1_SW1") (pintype "bidirectional"))
      (node (ref "U$4") (pin "SW1") (pinfunction "SW1_SW1") (pintype "bidirectional"))
      (node (ref "U$52") (pin "SW1") (pinfunction "SW1_SW1") (pintype "bidirectional"))
      (node (ref "U$68") (pin "SW1") (pinfunction "SW1_SW1") (pintype "bidirectional"))
    )
    (net (code "5") (name "/COL4") (class "Default")
      (node (ref "U$21") (pin "SW1") (pinfunction "SW1_SW1") (pintype "bidirectional"))
      (node (ref "U$30") (pin "27") (pinfunction "PD7(ADC10)_27") (pintype "bidirectional"))
      (node (ref "U$37") (pin "SW1") (pinfunction "SW1_SW1") (pintype "bidirectional"))
      (node (ref "U$5") (pin "SW1") (pinfunction "SW1_SW1") (pintype "bidirectional"))
      (node (ref "U$53") (pin "SW1") (pinfunction "SW1_SW1") (pintype "bidirectional"))
      (node (ref "U$69") (pin "SW1") (pinfunction "SW1_SW1") (pintype "bidirectional"))
    )
    (net (code "6") (name "/COL5") (class "Default")
      (node (ref "U$22") (pin "SW1") (pinfunction "SW1_SW1") (pintype "bidirectional"))
      (node (ref "U$30") (pin "1") (pinfunction "PE6_1") (pintype "bidirectional"))
      (node (ref "U$38") (pin "SW1") (pinfunction "SW1_SW1") (pintype "bidirectional"))
      (node (ref "U$54") (pin "SW1") (pinfunction "SW1_SW1") (pintype "bidirectional"))
      (node (ref "U$6") (pin "SW1") (pinfunction "SW1_SW1") (pintype "bidirectional"))
      (node (ref "U$70") (pin "SW1") (pinfunction "SW1_SW1") (pintype "bidirectional"))
      (node (ref "U$86") (pin "SW1") (pinfunction "SW1_SW1") (pintype "bidirectional"))
      (node (ref "U$89") (pin "SW1") (pinfunction "SW1_SW1") (pintype "bidirectional"))
    )
    (net (code "7") (name "/COL6") (class "Default")
      (node (ref "U$23") (pin "SW1") (pinfunction "SW1_SW1") (pintype "bidirectional"))
      (node (ref "U$30") (pin "28") (pinfunction "PB4(ADC11)_28") (pintype "bidirectional"))
      (node (ref "U$39") (pin "SW1") (pinfunction "SW1_SW1") (pintype "bidirectional"))
      (node (ref "U$55") (pin "SW1") (pinfunction "SW1_SW1") (pintype "bidirectional"))
      (node (ref "U$7") (pin "SW1") (pinfunction "SW1_SW1") (pintype "bidirectional"))
      (node (ref "U$71") (pin "SW1") (pinfunction "SW1_SW1") (pintype "bidirectional"))
    )
    (net (code "8") (name "/COL7") (class "Default")
      (node (ref "U$24") (pin "SW1") (pinfunction "SW1_SW1") (pintype "bidirectional"))
      (node (ref "U$30") (pin "29") (pinfunction "PB5(ADC12)_29") (pintype "bidirectional"))
      (node (ref "U$40") (pin "SW1") (pinfunction "SW1_SW1") (pintype "bidirectional"))
      (node (ref "U$56") (pin "SW1") (pinfunction "SW1_SW1") (pintype "bidirectional"))
      (node (ref "U$72") (pin "SW1") (pinfunction "SW1_SW1") (pintype "bidirectional"))
      (node (ref "U$8") (pin "SW1") (pinfunction "SW1_SW1") (pintype "bidirectional"))
    )
    (net (code "9") (name "/COL8") (class "Default")
      (node (ref "U$25") (pin "SW1") (pinfunction "SW1_SW1") (pintype "bidirectional"))
      (node (ref "U$30") (pin "30") (pinfunction "PB6(ADC13)_30") (pintype "bidirectional"))
      (node (ref "U$41") (pin "SW1") (pinfunction "SW1_SW1") (pintype "bidirectional"))
      (node (ref "U$57") (pin "SW1") (pinfunction "SW1_SW1") (pintype "bidirectional"))
      (node (ref "U$73") (pin "SW1") (pinfunction "SW1_SW1") (pintype "bidirectional"))
      (node (ref "U$9") (pin "SW1") (pinfunction "SW1_SW1") (pintype "bidirectional"))
    )
    (net (code "10") (name "/COL9") (class "Default")
      (node (ref "U$10") (pin "SW1") (pinfunction "SW1_SW1") (pintype "bidirectional"))
      (node (ref "U$26") (pin "SW1") (pinfunction "SW1_SW1") (pintype "bidirectional"))
      (node (ref "U$30") (pin "12") (pinfunction "PB7_12") (pintype "bidirectional"))
      (node (ref "U$42") (pin "SW1") (pinfunction "SW1_SW1") (pintype "bidirectional"))
      (node (ref "U$58") (pin "SW1") (pinfunction "SW1_SW1") (pintype "bidirectional"))
      (node (ref "U$74") (pin "SW1") (pinfunction "SW1_SW1") (pintype "bidirectional"))
    )
    (net (code "11") (name "/COL10") (class "Default")
      (node (ref "U$11") (pin "SW1") (pinfunction "SW1_SW1") (pintype "bidirectional"))
      (node (ref "U$27") (pin "SW1") (pinfunction "SW1_SW1") (pintype "bidirectional"))
      (node (ref "U$30") (pin "26") (pinfunction "PD6(ADC9)_26") (pintype "bidirectional"))
      (node (ref "U$43") (pin "SW1") (pinfunction "SW1_SW1") (pintype "bidirectional"))
      (node (ref "U$59") (pin "SW1") (pinfunction "SW1_SW1") (pintype "bidirectional"))
      (node (ref "U$75") (pin "SW1") (pinfunction "SW1_SW1") (pintype "bidirectional"))
    )
    (net (code "12") (name "/COL11") (class "Default")
      (node (ref "U$12") (pin "SW1") (pinfunction "SW1_SW1") (pintype "bidirectional"))
      (node (ref "U$28") (pin "SW1") (pinfunction "SW1_SW1") (pintype "bidirectional"))
      (node (ref "U$30") (pin "32") (pinfunction "PC7_32") (pintype "bidirectional"))
      (node (ref "U$44") (pin "SW1") (pinfunction "SW1_SW1") (pintype "bidirectional"))
      (node (ref "U$60") (pin "SW1") (pinfunction "SW1_SW1") (pintype "bidirectional"))
      (node (ref "U$76") (pin "SW1") (pinfunction "SW1_SW1") (pintype "bidirectional"))
      (node (ref "U$92") (pin "SW1") (pinfunction "SW1_SW1") (pintype "bidirectional"))
    )
    (net (code "13") (name "/COL12") (class "Default")
      (node (ref "U$13") (pin "SW1") (pinfunction "SW1_SW1") (pintype "bidirectional"))
      (node (ref "U$29") (pin "SW1") (pinfunction "SW1_SW1") (pintype "bidirectional"))
      (node (ref "U$30") (pin "8") (pinfunction "PB0(SS)_8") (pintype "bidirectional"))
      (node (ref "U$45") (pin "SW1") (pinfunction "SW1_SW1") (pintype "bidirectional"))
      (node (ref "U$61") (pin "SW1") (pinfunction "SW1_SW1") (pintype "bidirectional"))
      (node (ref "U$77") (pin "SW1") (pinfunction "SW1_SW1") (pintype "bidirectional"))
      (node (ref "U$93") (pin "SW1") (pinfunction "SW1_SW1") (pintype "bidirectional"))
    )
    (net (code "14") (name "/COL13") (class "Default")
      (node (ref "U$14") (pin "SW1") (pinfunction "SW1_SW1") (pintype "bidirectional"))
      (node (ref "U$30") (pin "9") (pinfunction "PB1(SCK)_9") (pintype "bidirectional"))
      (node (ref "U$94") (pin "SW1") (pinfunction "SW1_SW1") (pintype "bidirectional"))
    )
    (net (code "15") (name "/COL14") (class "Default")
      (node (ref "U$15") (pin "SW1") (pinfunction "SW1_SW1") (pintype "bidirectional"))
      (node (ref "U$30") (pin "10") (pinfunction "PB2(MOSI)_10") (pintype "bidirectional"))
      (node (ref "U$31") (pin "SW1") (pinfunction "SW1_SW1") (pintype "bidirectional"))
      (node (ref "U$47") (pin "SW1") (pinfunction "SW1_SW1") (pintype "bidirectional"))
      (node (ref "U$63") (pin "SW1") (pinfunction "SW1_SW1") (pintype "bidirectional"))
      (node (ref "U$79") (pin "SW1") (pinfunction "SW1_SW1") (pintype "bidirectional"))
      (node (ref "U$95") (pin "SW1") (pinfunction "SW1_SW1") (pintype "bidirectional"))
    )
    (net (code "16") (name "/COL15") (class "Default")
      (node (ref "U$16") (pin "SW1") (pinfunction "SW1_SW1") (pintype "bidirectional"))
      (node (ref "U$30") (pin "11") (pinfunction "PB3(MISO)_11") (pintype "bidirectional"))
      (node (ref "U$32") (pin "SW1") (pinfunction "SW1_SW1") (pintype "bidirectional"))
      (node (ref "U$48") (pin "SW1") (pinfunction "SW1_SW1") (pintype "bidirectional"))
      (node (ref "U$64") (pin "SW1") (pinfunction "SW1_SW1") (pintype "bidirectional"))
      (node (ref "U$80") (pin "SW1") (pinfunction "SW1_SW1") (pintype "bidirectional"))
      (node (ref "U$96") (pin "SW1") (pinfunction "SW1_SW1") (pintype "bidirectional"))
    )
    (net (code "17") (name "/ROW0") (class "Default")
      (node (ref "D1") (pin "C") (pinfunction "C_C") (pintype "passive"))
      (node (ref "D10") (pin "C") (pinfunction "C_C") (pintype "passive"))
      (node (ref "D11") (pin "C") (pinfunction "C_C") (pintype "passive"))
      (node (ref "D12") (pin "C") (pinfunction "C_C") (pintype "passive"))
      (node (ref "D13") (pin "C") (pinfunction "C_C") (pintype "passive"))
      (node (ref "D14") (pin "C") (pinfunction "C_C") (pintype "passive"))
      (node (ref "D15") (pin "C") (pinfunction "C_C") (pintype "passive"))
      (node (ref "D16") (pin "C") (pinfunction "C_C") (pintype "passive"))
      (node (ref "D2") (pin "C") (pinfunction "C_C") (pintype "passive"))
      (node (ref "D3") (pin "C") (pinfunction "C_C") (pintype "passive"))
      (node (ref "D4") (pin "C") (pinfunction "C_C") (pintype "passive"))
      (node (ref "D5") (pin "C") (pinfunction "C_C") (pintype "passive"))
      (node (ref "D6") (pin "C") (pinfunction "C_C") (pintype "passive"))
      (node (ref "D7") (pin "C") (pinfunction "C_C") (pintype "passive"))
      (node (ref "D8") (pin "C") (pinfunction "C_C") (pintype "passive"))
      (node (ref "D9") (pin "C") (pinfunction "C_C") (pintype "passive"))
      (node (ref "U$30") (pin "36") (pinfunction "PF7(ADC7)_36") (pintype "bidirectional"))
    )
    (net (code "18") (name "/ROW1") (class "Default")
      (node (ref "D17") (pin "C") (pinfunction "C_C") (pintype "passive"))
      (node (ref "D18") (pin "C") (pinfunction "C_C") (pintype "passive"))
      (node (ref "D19") (pin "C") (pinfunction "C_C") (pintype "passive"))
      (node (ref "D20") (pin "C") (pinfunction "C_C") (pintype "passive"))
      (node (ref "D21") (pin "C") (pinfunction "C_C") (pintype "passive"))
      (node (ref "D22") (pin "C") (pinfunction "C_C") (pintype "passive"))
      (node (ref "D23") (pin "C") (pinfunction "C_C") (pintype "passive"))
      (node (ref "D24") (pin "C") (pinfunction "C_C") (pintype "passive"))
      (node (ref "D25") (pin "C") (pinfunction "C_C") (pintype "passive"))
      (node (ref "D26") (pin "C") (pinfunction "C_C") (pintype "passive"))
      (node (ref "D27") (pin "C") (pinfunction "C_C") (pintype "passive"))
      (node (ref "D28") (pin "C") (pinfunction "C_C") (pintype "passive"))
      (node (ref "D29") (pin "C") (pinfunction "C_C") (pintype "passive"))
      (node (ref "D31") (pin "C") (pinfunction "C_C") (pintype "passive"))
      (node (ref "D32") (pin "C") (pinfunction "C_C") (pintype "passive"))
      (node (ref "U$30") (pin "37") (pinfunction "PF6(ADC6)_37") (pintype "bidirectional"))
    )
    (net (code "19") (name "/ROW2") (class "Default")
      (node (ref "D33") (pin "C") (pinfunction "C_C") (pintype "passive"))
      (node (ref "D34") (pin "C") (pinfunction "C_C") (pintype "passive"))
      (node (ref "D35") (pin "C") (pinfunction "C_C") (pintype "passive"))
      (node (ref "D36") (pin "C") (pinfunction "C_C") (pintype "passive"))
      (node (ref "D37") (pin "C") (pinfunction "C_C") (pintype "passive"))
      (node (ref "D38") (pin "C") (pinfunction "C_C") (pintype "passive"))
      (node (ref "D39") (pin "C") (pinfunction "C_C") (pintype "passive"))
      (node (ref "D40") (pin "C") (pinfunction "C_C") (pintype "passive"))
      (node (ref "D41") (pin "C") (pinfunction "C_C") (pintype "passive"))
      (node (ref "D42") (pin "C") (pinfunction "C_C") (pintype "passive"))
      (node (ref "D43") (pin "C") (pinfunction "C_C") (pintype "passive"))
      (node (ref "D44") (pin "C") (pinfunction "C_C") (pintype "passive"))
      (node (ref "D45") (pin "C") (pinfunction "C_C") (pintype "passive"))
      (node (ref "D47") (pin "C") (pinfunction "C_C") (pintype "passive"))
      (node (ref "D48") (pin "C") (pinfunction "C_C") (pintype "passive"))
      (node (ref "U$30") (pin "38") (pinfunction "PF5(ADC5)_38") (pintype "bidirectional"))
    )
    (net (code "20") (name "/ROW3") (class "Default")
      (node (ref "D49") (pin "C") (pinfunction "C_C") (pintype "passive"))
      (node (ref "D50") (pin "C") (pinfunction "C_C") (pintype "passive"))
      (node (ref "D51") (pin "C") (pinfunction "C_C") (pintype "passive"))
      (node (ref "D52") (pin "C") (pinfunction "C_C") (pintype "passive"))
      (node (ref "D53") (pin "C") (pinfunction "C_C") (pintype "passive"))
      (node (ref "D54") (pin "C") (pinfunction "C_C") (pintype "passive"))
      (node (ref "D55") (pin "C") (pinfunction "C_C") (pintype "passive"))
      (node (ref "D56") (pin "C") (pinfunction "C_C") (pintype "passive"))
      (node (ref "D57") (pin "C") (pinfunction "C_C") (pintype "passive"))
      (node (ref "D58") (pin "C") (pinfunction "C_C") (pintype "passive"))
      (node (ref "D59") (pin "C") (pinfunction "C_C") (pintype "passive"))
      (node (ref "D60") (pin "C") (pinfunction "C_C") (pintype "passive"))
      (node (ref "D61") (pin "C") (pinfunction "C_C") (pintype "passive"))
      (node (ref "D63") (pin "C") (pinfunction "C_C") (pintype "passive"))
      (node (ref "D64") (pin "C") (pinfunction "C_C") (pintype "passive"))
      (node (ref "U$30") (pin "39") (pinfunction "PF4(ADC4)_39") (pintype "bidirectional"))
    )
    (net (code "21") (name "/ROW4") (class "Default")
      (node (ref "D65") (pin "C") (pinfunction "C_C") (pintype "passive"))
      (node (ref "D66") (pin "C") (pinfunction "C_C") (pintype "passive"))
      (node (ref "D67") (pin "C") (pinfunction "C_C") (pintype "passive"))
      (node (ref "D68") (pin "C") (pinfunction "C_C") (pintype "passive"))
      (node (ref "D69") (pin "C") (pinfunction "C_C") (pintype "passive"))
      (node (ref "D70") (pin "C") (pinfunction "C_C") (pintype "passive"))
      (node (ref "D71") (pin "C") (pinfunction "C_C") (pintype "passive"))
      (node (ref "D72") (pin "C") (pinfunction "C_C") (pintype "passive"))
      (node (ref "D73") (pin "C") (pinfunction "C_C") (pintype "passive"))
      (node (ref "D74") (pin "C") (pinfunction "C_C") (pintype "passive"))
      (node (ref "D75") (pin "C") (pinfunction "C_C") (pintype "passive"))
      (node (ref "D76") (pin "C") (pinfunction "C_C") (pintype "passive"))
      (node (ref "D77") (pin "C") (pinfunction "C_C") (pintype "passive"))
      (node (ref "D79") (pin "C") (pinfunction "C_C") (pintype "passive"))
      (node (ref "D80") (pin "C") (pinfunction "C_C") (pintype "passive"))
      (node (ref "U$30") (pin "40") (pinfunction "PF1(ADC1)_40") (pintype "bidirectional"))
    )
    (net (code "22") (name "/ROW5") (class "Default")
      (node (ref "D30") (pin "C") (pinfunction "C_C") (pintype "passive"))
      (node (ref "D81") (pin "C") (pinfunction "C_C") (pintype "passive"))
      (node (ref "D82") (pin "C") (pinfunction "C_C") (pintype "passive"))
      (node (ref "D83") (pin "C") (pinfunction "C_C") (pintype "passive"))
      (node (ref "D86") (pin "C") (pinfunction "C_C") (pintype "passive"))
      (node (ref "D92") (pin "C") (pinfunction "C_C") (pintype "passive"))
      (node (ref "D93") (pin "C") (pinfunction "C_C") (pintype "passive"))
      (node (ref "D94") (pin "C") (pinfunction "C_C") (pintype "passive"))
      (node (ref "D95") (pin "C") (pinfunction "C_C") (pintype "passive"))
      (node (ref "D96") (pin "C") (pinfunction "C_C") (pintype "passive"))
      (node (ref "U$30") (pin "41") (pinfunction "PF0(ADC0)_41") (pintype "bidirectional"))
    )
    (net (code "23") (name "GND") (class "Default")
      (node (ref "C1") (pin "1") (pinfunction "1_1") (pintype "passive"))
      (node (ref "C2") (pin "2") (pinfunction "2_2") (pintype "passive"))
      (node (ref "C3") (pin "2") (pinfunction "2_2") (pintype "passive"))
      (node (ref "C4") (pin "2") (pinfunction "2_2") (pintype "passive"))
      (node (ref "C5") (pin "2") (pinfunction "2_2") (pintype "passive"))
      (node (ref "C6") (pin "2") (pinfunction "2_2") (pintype "passive"))
      (node (ref "C7") (pin "2") (pinfunction "2_2") (pintype "passive"))
      (node (ref "C8") (pin "2") (pinfunction "2_2") (pintype "passive"))
      (node (ref "CN1") (pin "GND") (pinfunction "GND_GND") (pintype "power_in"))
      (node (ref "R3") (pin "1") (pinfunction "1_1") (pintype "passive"))
      (node (ref "SW1") (pin "A") (pinfunction "P_A") (pintype "passive"))
      (node (ref "U$30") (pin "15") (pinfunction "GND_15") (pintype "bidirectional"))
      (node (ref "U$30") (pin "23") (pinfunction "GND_23") (pintype "bidirectional"))
      (node (ref "U$30") (pin "35") (pinfunction "GND_35") (pintype "bidirectional"))
      (node (ref "U$30") (pin "43") (pinfunction "GND_43") (pintype "bidirectional"))
      (node (ref "U$30") (pin "5") (pinfunction "UGND_5") (pintype "bidirectional"))
    )
    (net (code "24") (name "Net-(CN1-PadD+)") (class "Default")
      (node (ref "CN1") (pin "D+") (pinfunction "D+_D+") (pintype "bidirectional"))
      (node (ref "R1") (pin "1") (pinfunction "1_1") (pintype "passive"))
    )
    (net (code "25") (name "Net-(CN1-PadD-)") (class "Default")
      (node (ref "CN1") (pin "D-") (pinfunction "D-_D-") (pintype "bidirectional"))
      (node (ref "R2") (pin "1") (pinfunction "1_1") (pintype "passive"))
    )
    (net (code "26") (name "Net-(D1-PadA)") (class "Default")
      (node (ref "D1") (pin "A") (pinfunction "A_A") (pintype "passive"))
      (node (ref "U$1") (pin "SW2") (pinfunction "SW2_SW2") (pintype "bidirectional"))
    )
    (net (code "27") (name "Net-(D2-PadA)") (class "Default")
      (node (ref "D2") (pin "A") (pinfunction "A_A") (pintype "passive"))
      (node (ref "U$2") (pin "SW2") (pinfunction "SW2_SW2") (pintype "bidirectional"))
    )
    (net (code "28") (name "Net-(D3-PadA)") (class "Default")
      (node (ref "D3") (pin "A") (pinfunction "A_A") (pintype "passive"))
      (node (ref "U$3") (pin "SW2") (pinfunction "SW2_SW2") (pintype "bidirectional"))
    )
    (net (code "29") (name "Net-(D4-PadA)") (class "Default")
      (node (ref "D4") (pin "A") (pinfunction "A_A") (pintype "passive"))
      (node (ref "U$4") (pin "SW2") (pinfunction "SW2_SW2") (pintype "bidirectional"))
    )
    (net (code "30") (name "Net-(D5-PadA)") (class "Default")
      (node (ref "D5") (pin "A") (pinfunction "A_A") (pintype "passive"))
      (node (ref "U$5") (pin "SW2") (pinfunction "SW2_SW2") (pintype "bidirectional"))
    )
    (net (code "31") (name "Net-(D6-PadA)") (class "Default")
      (node (ref "D6") (pin "A") (pinfunction "A_A") (pintype "passive"))
      (node (ref "U$6") (pin "SW2") (pinfunction "SW2_SW2") (pintype "bidirectional"))
    )
    (net (code "32") (name "Net-(D7-PadA)") (class "Default")
      (node (ref "D7") (pin "A") (pinfunction "A_A") (pintype "passive"))
      (node (ref "U$7") (pin "SW2") (pinfunction "SW2_SW2") (pintype "bidirectional"))
    )
    (net (code "33") (name "Net-(D8-PadA)") (class "Default")
      (node (ref "D8") (pin "A") (pinfunction "A_A") (pintype "passive"))
      (node (ref "U$8") (pin "SW2") (pinfunction "SW2_SW2") (pintype "bidirectional"))
    )
    (net (code "34") (name "Net-(D9-PadA)") (class "Default")
      (node (ref "D9") (pin "A") (pinfunction "A_A") (pintype "passive"))
      (node (ref "U$9") (pin "SW2") (pinfunction "SW2_SW2") (pintype "bidirectional"))
    )
    (net (code "35") (name "Net-(D10-PadA)") (class "Default")
      (node (ref "D10") (pin "A") (pinfunction "A_A") (pintype "passive"))
      (node (ref "U$10") (pin "SW2") (pinfunction "SW2_SW2") (pintype "bidirectional"))
    )
    (net (code "36") (name "Net-(D11-PadA)") (class "Default")
      (node (ref "D11") (pin "A") (pinfunction "A_A") (pintype "passive"))
      (node (ref "U$11") (pin "SW2") (pinfunction "SW2_SW2") (pintype "bidirectional"))
    )
    (net (code "37") (name "Net-(D12-PadA)") (class "Default")
      (node (ref "D12") (pin "A") (pinfunction "A_A") (pintype "passive"))
      (node (ref "U$12") (pin "SW2") (pinfunction "SW2_SW2") (pintype "bidirectional"))
    )
    (net (code "38") (name "Net-(D13-PadA)") (class "Default")
      (node (ref "D13") (pin "A") (pinfunction "A_A") (pintype "passive"))
      (node (ref "U$13") (pin "SW2") (pinfunction "SW2_SW2") (pintype "bidirectional"))
    )
    (net (code "39") (name "Net-(D14-PadA)") (class "Default")
      (node (ref "D14") (pin "A") (pinfunction "A_A") (pintype "passive"))
      (node (ref "U$14") (pin "SW2") (pinfunction "SW2_SW2") (pintype "bidirectional"))
    )
    (net (code "40") (name "Net-(D15-PadA)") (class "Default")
      (node (ref "D15") (pin "A") (pinfunction "A_A") (pintype "passive"))
      (node (ref "U$15") (pin "SW2") (pinfunction "SW2_SW2") (pintype "bidirectional"))
    )
    (net (code "41") (name "Net-(D16-PadA)") (class "Default")
      (node (ref "D16") (pin "A") (pinfunction "A_A") (pintype "passive"))
      (node (ref "U$16") (pin "SW2") (pinfunction "SW2_SW2") (pintype "bidirectional"))
    )
    (net (code "42") (name "Net-(D17-PadA)") (class "Default")
      (node (ref "D17") (pin "A") (pinfunction "A_A") (pintype "passive"))
      (node (ref "U$17") (pin "SW2") (pinfunction "SW2_SW2") (pintype "bidirectional"))
    )
    (net (code "43") (name "Net-(D18-PadA)") (class "Default")
      (node (ref "D18") (pin "A") (pinfunction "A_A") (pintype "passive"))
      (node (ref "U$18") (pin "SW2") (pinfunction "SW2_SW2") (pintype "bidirectional"))
    )
    (net (code "44") (name "Net-(D19-PadA)") (class "Default")
      (node (ref "D19") (pin "A") (pinfunction "A_A") (pintype "passive"))
      (node (ref "U$19") (pin "SW2") (pinfunction "SW2_SW2") (pintype "bidirectional"))
    )
    (net (code "45") (name "Net-(D20-PadA)") (class "Default")
      (node (ref "D20") (pin "A") (pinfunction "A_A") (pintype "passive"))
      (node (ref "U$20") (pin "SW2") (pinfunction "SW2_SW2") (pintype "bidirectional"))
    )
    (net (code "46") (name "Net-(D21-PadA)") (class "Default")
      (node (ref "D21") (pin "A") (pinfunction "A_A") (pintype "passive"))
      (node (ref "U$21") (pin "SW2") (pinfunction "SW2_SW2") (pintype "bidirectional"))
    )
    (net (code "47") (name "Net-(D22-PadA)") (class "Default")
      (node (ref "D22") (pin "A") (pinfunction "A_A") (pintype "passive"))
      (node (ref "U$22") (pin "SW2") (pinfunction "SW2_SW2") (pintype "bidirectional"))
    )
    (net (code "48") (name "Net-(D23-PadA)") (class "Default")
      (node (ref "D23") (pin "A") (pinfunction "A_A") (pintype "passive"))
      (node (ref "U$23") (pin "SW2") (pinfunction "SW2_SW2") (pintype "bidirectional"))
    )
    (net (code "49") (name "Net-(D24-PadA)") (class "Default")
      (node (ref "D24") (pin "A") (pinfunction "A_A") (pintype "passive"))
      (node (ref "U$24") (pin "SW2") (pinfunction "SW2_SW2") (pintype "bidirectional"))
    )
    (net (code "50") (name "Net-(D25-PadA)") (class "Default")
      (node (ref "D25") (pin "A") (pinfunction "A_A") (pintype "passive"))
      (node (ref "U$25") (pin "SW2") (pinfunction "SW2_SW2") (pintype "bidirectional"))
    )
    (net (code "51") (name "Net-(D26-PadA)") (class "Default")
      (node (ref "D26") (pin "A") (pinfunction "A_A") (pintype "passive"))
      (node (ref "U$26") (pin "SW2") (pinfunction "SW2_SW2") (pintype "bidirectional"))
    )
    (net (code "52") (name "Net-(D27-PadA)") (class "Default")
      (node (ref "D27") (pin "A") (pinfunction "A_A") (pintype "passive"))
      (node (ref "U$27") (pin "SW2") (pinfunction "SW2_SW2") (pintype "bidirectional"))
    )
    (net (code "53") (name "Net-(D28-PadA)") (class "Default")
      (node (ref "D28") (pin "A") (pinfunction "A_A") (pintype "passive"))
      (node (ref "U$28") (pin "SW2") (pinfunction "SW2_SW2") (pintype "bidirectional"))
    )
    (net (code "54") (name "Net-(D29-PadA)") (class "Default")
      (node (ref "D29") (pin "A") (pinfunction "A_A") (pintype "passive"))
      (node (ref "U$29") (pin "SW2") (pinfunction "SW2_SW2") (pintype "bidirectional"))
    )
    (net (code "55") (name "Net-(D30-PadA)") (class "Default")
      (node (ref "D30") (pin "A") (pinfunction "A_A") (pintype "passive"))
      (node (ref "U$89") (pin "SW2") (pinfunction "SW2_SW2") (pintype "bidirectional"))
    )
    (net (code "56") (name "Net-(D31-PadA)") (class "Default")
      (node (ref "D31") (pin "A") (pinfunction "A_A") (pintype "passive"))
      (node (ref "U$31") (pin "SW2") (pinfunction "SW2_SW2") (pintype "bidirectional"))
    )
    (net (code "57") (name "Net-(D32-PadA)") (class "Default")
      (node (ref "D32") (pin "A") (pinfunction "A_A") (pintype "passive"))
      (node (ref "U$32") (pin "SW2") (pinfunction "SW2_SW2") (pintype "bidirectional"))
    )
    (net (code "58") (name "Net-(D33-PadA)") (class "Default")
      (node (ref "D33") (pin "A") (pinfunction "A_A") (pintype "passive"))
      (node (ref "U$33") (pin "SW2") (pinfunction "SW2_SW2") (pintype "bidirectional"))
    )
    (net (code "59") (name "Net-(D34-PadA)") (class "Default")
      (node (ref "D34") (pin "A") (pinfunction "A_A") (pintype "passive"))
      (node (ref "U$34") (pin "SW2") (pinfunction "SW2_SW2") (pintype "bidirectional"))
    )
    (net (code "60") (name "Net-(D35-PadA)") (class "Default")
      (node (ref "D35") (pin "A") (pinfunction "A_A") (pintype "passive"))
      (node (ref "U$35") (pin "SW2") (pinfunction "SW2_SW2") (pintype "bidirectional"))
    )
    (net (code "61") (name "Net-(D36-PadA)") (class "Default")
      (node (ref "D36") (pin "A") (pinfunction "A_A") (pintype "passive"))
      (node (ref "U$36") (pin "SW2") (pinfunction "SW2_SW2") (pintype "bidirectional"))
    )
    (net (code "62") (name "Net-(D37-PadA)") (class "Default")
      (node (ref "D37") (pin "A") (pinfunction "A_A") (pintype "passive"))
      (node (ref "U$37") (pin "SW2") (pinfunction "SW2_SW2") (pintype "bidirectional"))
    )
    (net (code "63") (name "Net-(D38-PadA)") (class "Default")
      (node (ref "D38") (pin "A") (pinfunction "A_A") (pintype "passive"))
      (node (ref "U$38") (pin "SW2") (pinfunction "SW2_SW2") (pintype "bidirectional"))
    )
    (net (code "64") (name "Net-(D39-PadA)") (class "Default")
      (node (ref "D39") (pin "A") (pinfunction "A_A") (pintype "passive"))
      (node (ref "U$39") (pin "SW2") (pinfunction "SW2_SW2") (pintype "bidirectional"))
    )
    (net (code "65") (name "Net-(D40-PadA)") (class "Default")
      (node (ref "D40") (pin "A") (pinfunction "A_A") (pintype "passive"))
      (node (ref "U$40") (pin "SW2") (pinfunction "SW2_SW2") (pintype "bidirectional"))
    )
    (net (code "66") (name "Net-(D41-PadA)") (class "Default")
      (node (ref "D41") (pin "A") (pinfunction "A_A") (pintype "passive"))
      (node (ref "U$41") (pin "SW2") (pinfunction "SW2_SW2") (pintype "bidirectional"))
    )
    (net (code "67") (name "Net-(D42-PadA)") (class "Default")
      (node (ref "D42") (pin "A") (pinfunction "A_A") (pintype "passive"))
      (node (ref "U$42") (pin "SW2") (pinfunction "SW2_SW2") (pintype "bidirectional"))
    )
    (net (code "68") (name "Net-(D43-PadA)") (class "Default")
      (node (ref "D43") (pin "A") (pinfunction "A_A") (pintype "passive"))
      (node (ref "U$43") (pin "SW2") (pinfunction "SW2_SW2") (pintype "bidirectional"))
    )
    (net (code "69") (name "Net-(D44-PadA)") (class "Default")
      (node (ref "D44") (pin "A") (pinfunction "A_A") (pintype "passive"))
      (node (ref "U$44") (pin "SW2") (pinfunction "SW2_SW2") (pintype "bidirectional"))
    )
    (net (code "70") (name "Net-(D45-PadA)") (class "Default")
      (node (ref "D45") (pin "A") (pinfunction "A_A") (pintype "passive"))
      (node (ref "U$45") (pin "SW2") (pinfunction "SW2_SW2") (pintype "bidirectional"))
    )
    (net (code "71") (name "Net-(D47-PadA)") (class "Default")
      (node (ref "D47") (pin "A") (pinfunction "A_A") (pintype "passive"))
      (node (ref "U$47") (pin "SW2") (pinfunction "SW2_SW2") (pintype "bidirectional"))
    )
    (net (code "72") (name "Net-(D48-PadA)") (class "Default")
      (node (ref "D48") (pin "A") (pinfunction "A_A") (pintype "passive"))
      (node (ref "U$48") (pin "SW2") (pinfunction "SW2_SW2") (pintype "bidirectional"))
    )
    (net (code "73") (name "Net-(D49-PadA)") (class "Default")
      (node (ref "D49") (pin "A") (pinfunction "A_A") (pintype "passive"))
      (node (ref "U$49") (pin "SW2") (pinfunction "SW2_SW2") (pintype "bidirectional"))
    )
    (net (code "74") (name "Net-(D50-PadA)") (class "Default")
      (node (ref "D50") (pin "A") (pinfunction "A_A") (pintype "passive"))
      (node (ref "U$50") (pin "SW2") (pinfunction "SW2_SW2") (pintype "bidirectional"))
    )
    (net (code "75") (name "Net-(D51-PadA)") (class "Default")
      (node (ref "D51") (pin "A") (pinfunction "A_A") (pintype "passive"))
      (node (ref "U$51") (pin "SW2") (pinfunction "SW2_SW2") (pintype "bidirectional"))
    )
    (net (code "76") (name "Net-(D52-PadA)") (class "Default")
      (node (ref "D52") (pin "A") (pinfunction "A_A") (pintype "passive"))
      (node (ref "U$52") (pin "SW2") (pinfunction "SW2_SW2") (pintype "bidirectional"))
    )
    (net (code "77") (name "Net-(D53-PadA)") (class "Default")
      (node (ref "D53") (pin "A") (pinfunction "A_A") (pintype "passive"))
      (node (ref "U$53") (pin "SW2") (pinfunction "SW2_SW2") (pintype "bidirectional"))
    )
    (net (code "78") (name "Net-(D54-PadA)") (class "Default")
      (node (ref "D54") (pin "A") (pinfunction "A_A") (pintype "passive"))
      (node (ref "U$54") (pin "SW2") (pinfunction "SW2_SW2") (pintype "bidirectional"))
    )
    (net (code "79") (name "Net-(D55-PadA)") (class "Default")
      (node (ref "D55") (pin "A") (pinfunction "A_A") (pintype "passive"))
      (node (ref "U$55") (pin "SW2") (pinfunction "SW2_SW2") (pintype "bidirectional"))
    )
    (net (code "80") (name "Net-(D56-PadA)") (class "Default")
      (node (ref "D56") (pin "A") (pinfunction "A_A") (pintype "passive"))
      (node (ref "U$56") (pin "SW2") (pinfunction "SW2_SW2") (pintype "bidirectional"))
    )
    (net (code "81") (name "Net-(D57-PadA)") (class "Default")
      (node (ref "D57") (pin "A") (pinfunction "A_A") (pintype "passive"))
      (node (ref "U$57") (pin "SW2") (pinfunction "SW2_SW2") (pintype "bidirectional"))
    )
    (net (code "82") (name "Net-(D58-PadA)") (class "Default")
      (node (ref "D58") (pin "A") (pinfunction "A_A") (pintype "passive"))
      (node (ref "U$58") (pin "SW2") (pinfunction "SW2_SW2") (pintype "bidirectional"))
    )
    (net (code "83") (name "Net-(D59-PadA)") (class "Default")
      (node (ref "D59") (pin "A") (pinfunction "A_A") (pintype "passive"))
      (node (ref "U$59") (pin "SW2") (pinfunction "SW2_SW2") (pintype "bidirectional"))
    )
    (net (code "84") (name "Net-(D60-PadA)") (class "Default")
      (node (ref "D60") (pin "A") (pinfunction "A_A") (pintype "passive"))
      (node (ref "U$60") (pin "SW2") (pinfunction "SW2_SW2") (pintype "bidirectional"))
    )
    (net (code "85") (name "Net-(D61-PadA)") (class "Default")
      (node (ref "D61") (pin "A") (pinfunction "A_A") (pintype "passive"))
      (node (ref "U$61") (pin "SW2") (pinfunction "SW2_SW2") (pintype "bidirectional"))
    )
    (net (code "86") (name "Net-(D63-PadA)") (class "Default")
      (node (ref "D63") (pin "A") (pinfunction "A_A") (pintype "passive"))
      (node (ref "U$63") (pin "SW2") (pinfunction "SW2_SW2") (pintype "bidirectional"))
    )
    (net (code "87") (name "Net-(D64-PadA)") (class "Default")
      (node (ref "D64") (pin "A") (pinfunction "A_A") (pintype "passive"))
      (node (ref "U$64") (pin "SW2") (pinfunction "SW2_SW2") (pintype "bidirectional"))
    )
    (net (code "88") (name "Net-(D65-PadA)") (class "Default")
      (node (ref "D65") (pin "A") (pinfunction "A_A") (pintype "passive"))
      (node (ref "U$65") (pin "SW2") (pinfunction "SW2_SW2") (pintype "bidirectional"))
    )
    (net (code "89") (name "Net-(D66-PadA)") (class "Default")
      (node (ref "D66") (pin "A") (pinfunction "A_A") (pintype "passive"))
      (node (ref "U$66") (pin "SW2") (pinfunction "SW2_SW2") (pintype "bidirectional"))
    )
    (net (code "90") (name "Net-(D67-PadA)") (class "Default")
      (node (ref "D67") (pin "A") (pinfunction "A_A") (pintype "passive"))
      (node (ref "U$67") (pin "SW2") (pinfunction "SW2_SW2") (pintype "bidirectional"))
    )
    (net (code "91") (name "Net-(D68-PadA)") (class "Default")
      (node (ref "D68") (pin "A") (pinfunction "A_A") (pintype "passive"))
      (node (ref "U$68") (pin "SW2") (pinfunction "SW2_SW2") (pintype "bidirectional"))
    )
    (net (code "92") (name "Net-(D69-PadA)") (class "Default")
      (node (ref "D69") (pin "A") (pinfunction "A_A") (pintype "passive"))
      (node (ref "U$69") (pin "SW2") (pinfunction "SW2_SW2") (pintype "bidirectional"))
    )
    (net (code "93") (name "Net-(D70-PadA)") (class "Default")
      (node (ref "D70") (pin "A") (pinfunction "A_A") (pintype "passive"))
      (node (ref "U$70") (pin "SW2") (pinfunction "SW2_SW2") (pintype "bidirectional"))
    )
    (net (code "94") (name "Net-(D71-PadA)") (class "Default")
      (node (ref "D71") (pin "A") (pinfunction "A_A") (pintype "passive"))
      (node (ref "U$71") (pin "SW2") (pinfunction "SW2_SW2") (pintype "bidirectional"))
    )
    (net (code "95") (name "Net-(D72-PadA)") (class "Default")
      (node (ref "D72") (pin "A") (pinfunction "A_A") (pintype "passive"))
      (node (ref "U$72") (pin "SW2") (pinfunction "SW2_SW2") (pintype "bidirectional"))
    )
    (net (code "96") (name "Net-(D73-PadA)") (class "Default")
      (node (ref "D73") (pin "A") (pinfunction "A_A") (pintype "passive"))
      (node (ref "U$73") (pin "SW2") (pinfunction "SW2_SW2") (pintype "bidirectional"))
    )
    (net (code "97") (name "Net-(D74-PadA)") (class "Default")
      (node (ref "D74") (pin "A") (pinfunction "A_A") (pintype "passive"))
      (node (ref "U$74") (pin "SW2") (pinfunction "SW2_SW2") (pintype "bidirectional"))
    )
    (net (code "98") (name "Net-(D75-PadA)") (class "Default")
      (node (ref "D75") (pin "A") (pinfunction "A_A") (pintype "passive"))
      (node (ref "U$75") (pin "SW2") (pinfunction "SW2_SW2") (pintype "bidirectional"))
    )
    (net (code "99") (name "Net-(D76-PadA)") (class "Default")
      (node (ref "D76") (pin "A") (pinfunction "A_A") (pintype "passive"))
      (node (ref "U$76") (pin "SW2") (pinfunction "SW2_SW2") (pintype "bidirectional"))
    )
    (net (code "100") (name "Net-(D77-PadA)") (class "Default")
      (node (ref "D77") (pin "A") (pinfunction "A_A") (pintype "passive"))
      (node (ref "U$77") (pin "SW2") (pinfunction "SW2_SW2") (pintype "bidirectional"))
    )
    (net (code "101") (name "Net-(D79-PadA)") (class "Default")
      (node (ref "D79") (pin "A") (pinfunction "A_A") (pintype "passive"))
      (node (ref "U$79") (pin "SW2") (pinfunction "SW2_SW2") (pintype "bidirectional"))
    )
    (net (code "102") (name "Net-(D80-PadA)") (class "Default")
      (node (ref "D80") (pin "A") (pinfunction "A_A") (pintype "passive"))
      (node (ref "U$80") (pin "SW2") (pinfunction "SW2_SW2") (pintype "bidirectional"))
    )
    (net (code "103") (name "Net-(D81-PadA)") (class "Default")
      (node (ref "D81") (pin "A") (pinfunction "A_A") (pintype "passive"))
      (node (ref "U$81") (pin "SW2") (pinfunction "SW2_SW2") (pintype "bidirectional"))
    )
    (net (code "104") (name "Net-(D82-PadA)") (class "Default")
      (node (ref "D82") (pin "A") (pinfunction "A_A") (pintype "passive"))
      (node (ref "U$82") (pin "SW2") (pinfunction "SW2_SW2") (pintype "bidirectional"))
    )
    (net (code "105") (name "Net-(D83-PadA)") (class "Default")
      (node (ref "D83") (pin "A") (pinfunction "A_A") (pintype "passive"))
      (node (ref "U$83") (pin "SW2") (pinfunction "SW2_SW2") (pintype "bidirectional"))
    )
    (net (code "106") (name "Net-(D86-PadA)") (class "Default")
      (node (ref "D86") (pin "A") (pinfunction "A_A") (pintype "passive"))
      (node (ref "U$86") (pin "SW2") (pinfunction "SW2_SW2") (pintype "bidirectional"))
    )
    (net (code "107") (name "Net-(D92-PadA)") (class "Default")
      (node (ref "D92") (pin "A") (pinfunction "A_A") (pintype "passive"))
      (node (ref "U$92") (pin "SW2") (pinfunction "SW2_SW2") (pintype "bidirectional"))
    )
    (net (code "108") (name "Net-(D93-PadA)") (class "Default")
      (node (ref "D93") (pin "A") (pinfunction "A_A") (pintype "passive"))
      (node (ref "U$93") (pin "SW2") (pinfunction "SW2_SW2") (pintype "bidirectional"))
    )
    (net (code "109") (name "Net-(D94-PadA)") (class "Default")
      (node (ref "D94") (pin "A") (pinfunction "A_A") (pintype "passive"))
      (node (ref "U$94") (pin "SW2") (pinfunction "SW2_SW2") (pintype "bidirectional"))
    )
    (net (code "110") (name "Net-(D95-PadA)") (class "Default")
      (node (ref "D95") (pin "A") (pinfunction "A_A") (pintype "passive"))
      (node (ref "U$95") (pin "SW2") (pinfunction "SW2_SW2") (pintype "bidirectional"))
    )
    (net (code "111") (name "Net-(D96-PadA)") (class "Default")
      (node (ref "D96") (pin "A") (pinfunction "A_A") (pintype "passive"))
      (node (ref "U$96") (pin "SW2") (pinfunction "SW2_SW2") (pintype "bidirectional"))
    )
    (net (code "112") (name "Net-(SW1-S)") (class "Default")
      (node (ref "R4") (pin "1") (pinfunction "1_1") (pintype "passive"))
      (node (ref "SW1") (pin "B") (pinfunction "S_B") (pintype "passive"))
      (node (ref "U$30") (pin "13") (pinfunction "~{RESET}_13") (pintype "bidirectional"))
    )
    (net (code "113") (name "Net-(U$30-D+)") (class "Default")
      (node (ref "R1") (pin "2") (pinfunction "2_2") (pintype "passive"))
      (node (ref "U$30") (pin "4") (pinfunction "D+_4") (pintype "bidirectional"))
    )
    (net (code "114") (name "Net-(U$30-D-)") (class "Default")
      (node (ref "R2") (pin "2") (pinfunction "2_2") (pintype "passive"))
      (node (ref "U$30") (pin "3") (pinfunction "D-_3") (pintype "bidirectional"))
    )
    (net (code "115") (name "Net-(U$30-PE2{slash}~{HWB})") (class "Default")
      (node (ref "R3") (pin "2") (pinfunction "2_2") (pintype "passive"))
      (node (ref "U$30") (pin "33") (pinfunction "PE2/~{HWB}_33") (pintype "bidirectional"))
    )
    (net (code "116") (name "Net-(U$30-UCAP)") (class "Default")
      (node (ref "C1") (pin "2") (pinfunction "2_2") (pintype "passive"))
      (node (ref "U$30") (pin "6") (pinfunction "UCAP_6") (pintype "bidirectional"))
    )
    (net (code "117") (name "Net-(U$30-XTAL1)") (class "Default")
      (node (ref "C2") (pin "1") (pinfunction "1_1") (pintype "passive"))
      (node (ref "Q1") (pin "1") (pinfunction "1_1") (pintype "passive"))
      (node (ref "U$30") (pin "17") (pinfunction "XTAL1_17") (pintype "bidirectional"))
    )
    (net (code "118") (name "Net-(U$30-XTAL2)") (class "Default")
      (node (ref "C3") (pin "1") (pinfunction "1_1") (pintype "passive"))
      (node (ref "Q1") (pin "2") (pinfunction "2_2") (pintype "passive"))
      (node (ref "U$30") (pin "16") (pinfunction "XTAL2_16") (pintype "bidirectional"))
    )
    (net (code "119") (name "VCC") (class "Default")
      (node (ref "C4") (pin "1") (pinfunction "1_1") (pintype "passive"))
      (node (ref "C5") (pin "1") (pinfunction "1_1") (pintype "passive"))
      (node (ref "C6") (pin "1") (pinfunction "1_1") (pintype "passive"))
      (node (ref "C7") (pin "1") (pinfunction "1_1") (pintype "passive"))
      (node (ref "C8") (pin "1") (pinfunction "1_1") (pintype "passive"))
      (node (ref "CN1") (pin "VBUS") (pinfunction "VBUS_VBUS") (pintype "power_in"))
      (node (ref "R4") (pin "2") (pinfunction "2_2") (pintype "passive"))
      (node (ref "U$30") (pin "14") (pinfunction "VCC_14") (pintype "bidirectional"))
      (node (ref "U$30") (pin "2") (pinfunction "UVCC_2") (pintype "bidirectional"))
      (node (ref "U$30") (pin "24") (pinfunction "AVCC_24") (pintype "bidirectional"))
      (node (ref "U$30") (pin "34") (pinfunction "VCC_34") (pintype "bidirectional"))
      (node (ref "U$30") (pin "44") (pinfunction "AVCC_44") (pintype "bidirectional"))
      (node (ref "U$30") (pin "7") (pinfunction "VBUS_7") (pintype "bidirectional"))
    )
    (net (code "120") (name "unconnected-(CN1-PadID)") (class "Default")
      (node (ref "CN1") (pin "ID") (pinfunction "ID_ID") (pintype "bidirectional"))
    )
    (net (code "121") (name "unconnected-(SW1-P1-PadA')") (class "Default")
      (node (ref "SW1") (pin "A'") (pinfunction "P1_A'") (pintype "passive"))
    )
    (net (code "122") (name "unconnected-(SW1-S1-PadB')") (class "Default")
      (node (ref "SW1") (pin "B'") (pinfunction "S1_B'") (pintype "passive"))
    )
    (net (code "123") (name "unconnected-(U$30-AREF-Pad42)") (class "Default")
      (node (ref "U$30") (pin "42") (pinfunction "AREF_42") (pintype "bidirectional"))
    )
    (net (code "124") (name "unconnected-(U$30-PD0(SCL)-Pad18)") (class "Default")
      (node (ref "U$30") (pin "18") (pinfunction "PD0(SCL)_18") (pintype "bidirectional"))
    )
    (net (code "125") (name "unconnected-(U$30-PD1(SDA)-Pad19)") (class "Default")
      (node (ref "U$30") (pin "19") (pinfunction "PD1(SDA)_19") (pintype "bidirectional"))
    )
    (net (code "126") (name "unconnected-(U$30-PD5-Pad22)") (class "Default")
      (node (ref "U$30") (pin "22") (pinfunction "PD5_22") (pintype "bidirectional"))
    )
  )
)
